# rs485.net
KiCad netlist of a schematic drawn in Altium Designer
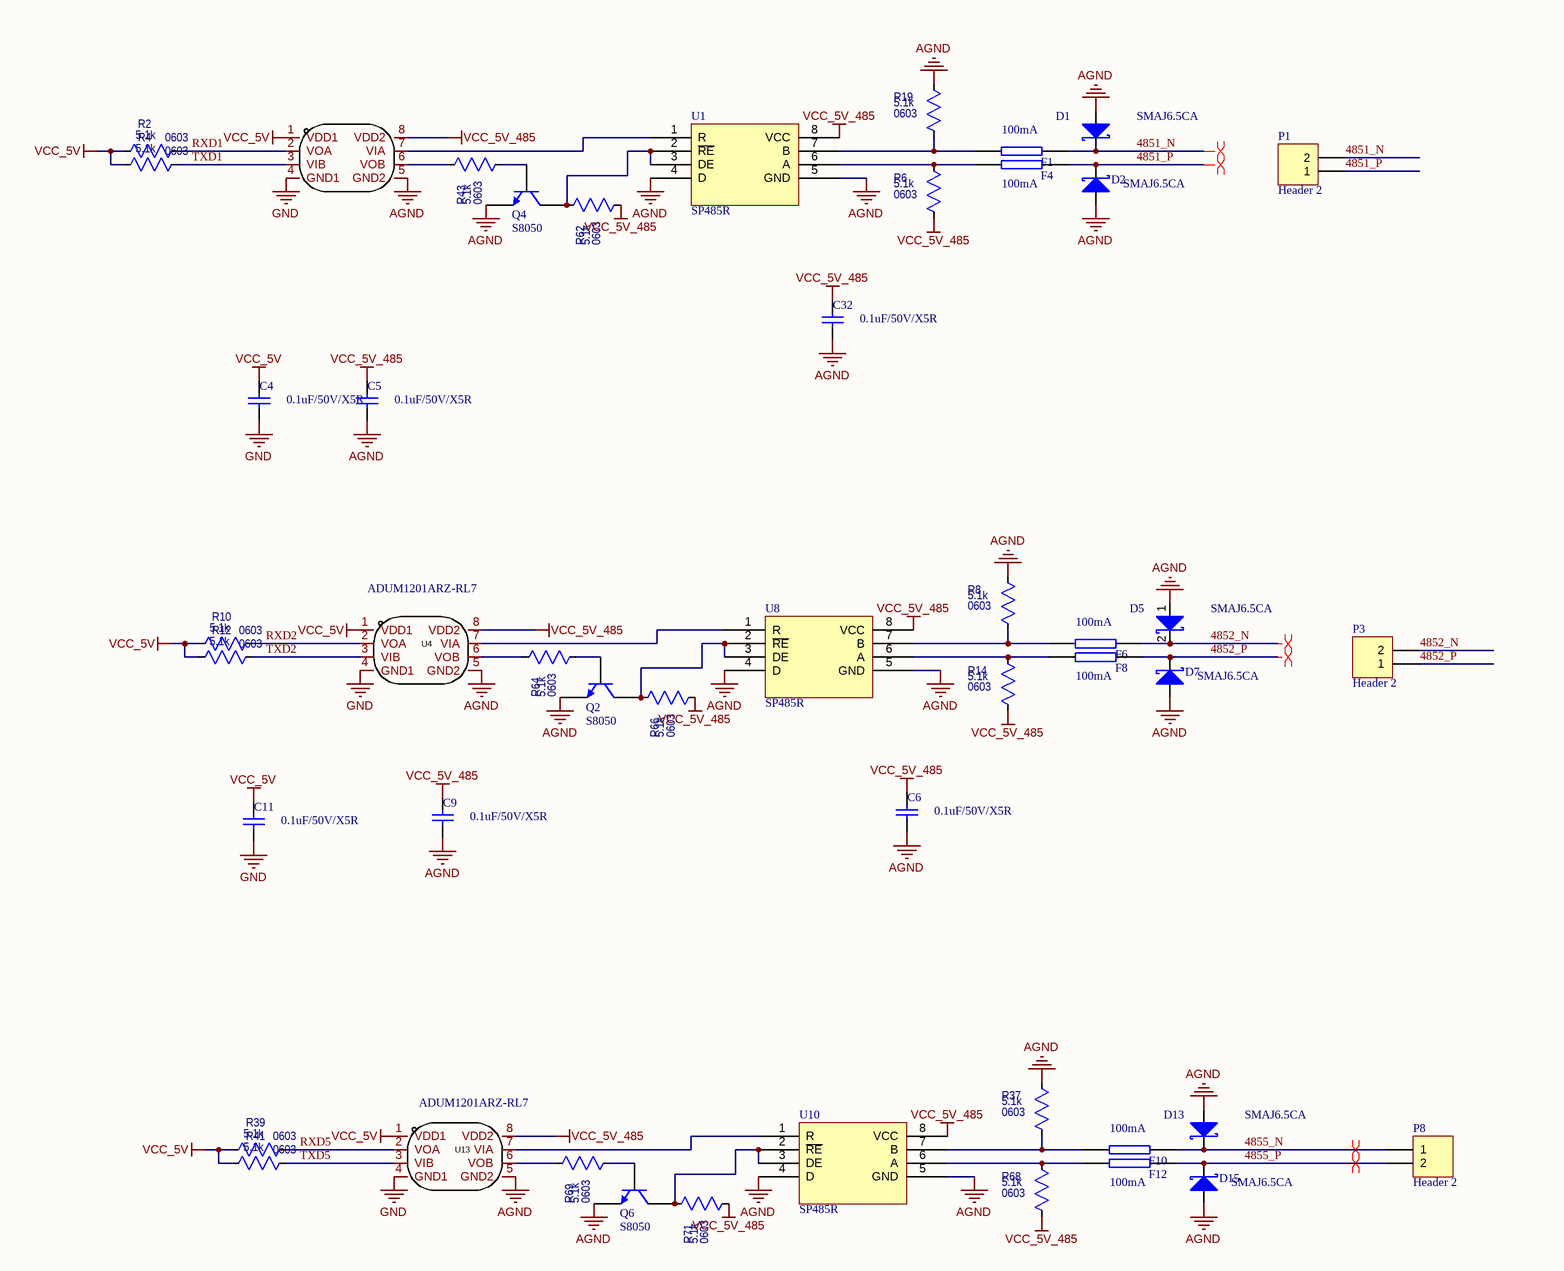
[diagram p0: rs485.SchDoc, top left]
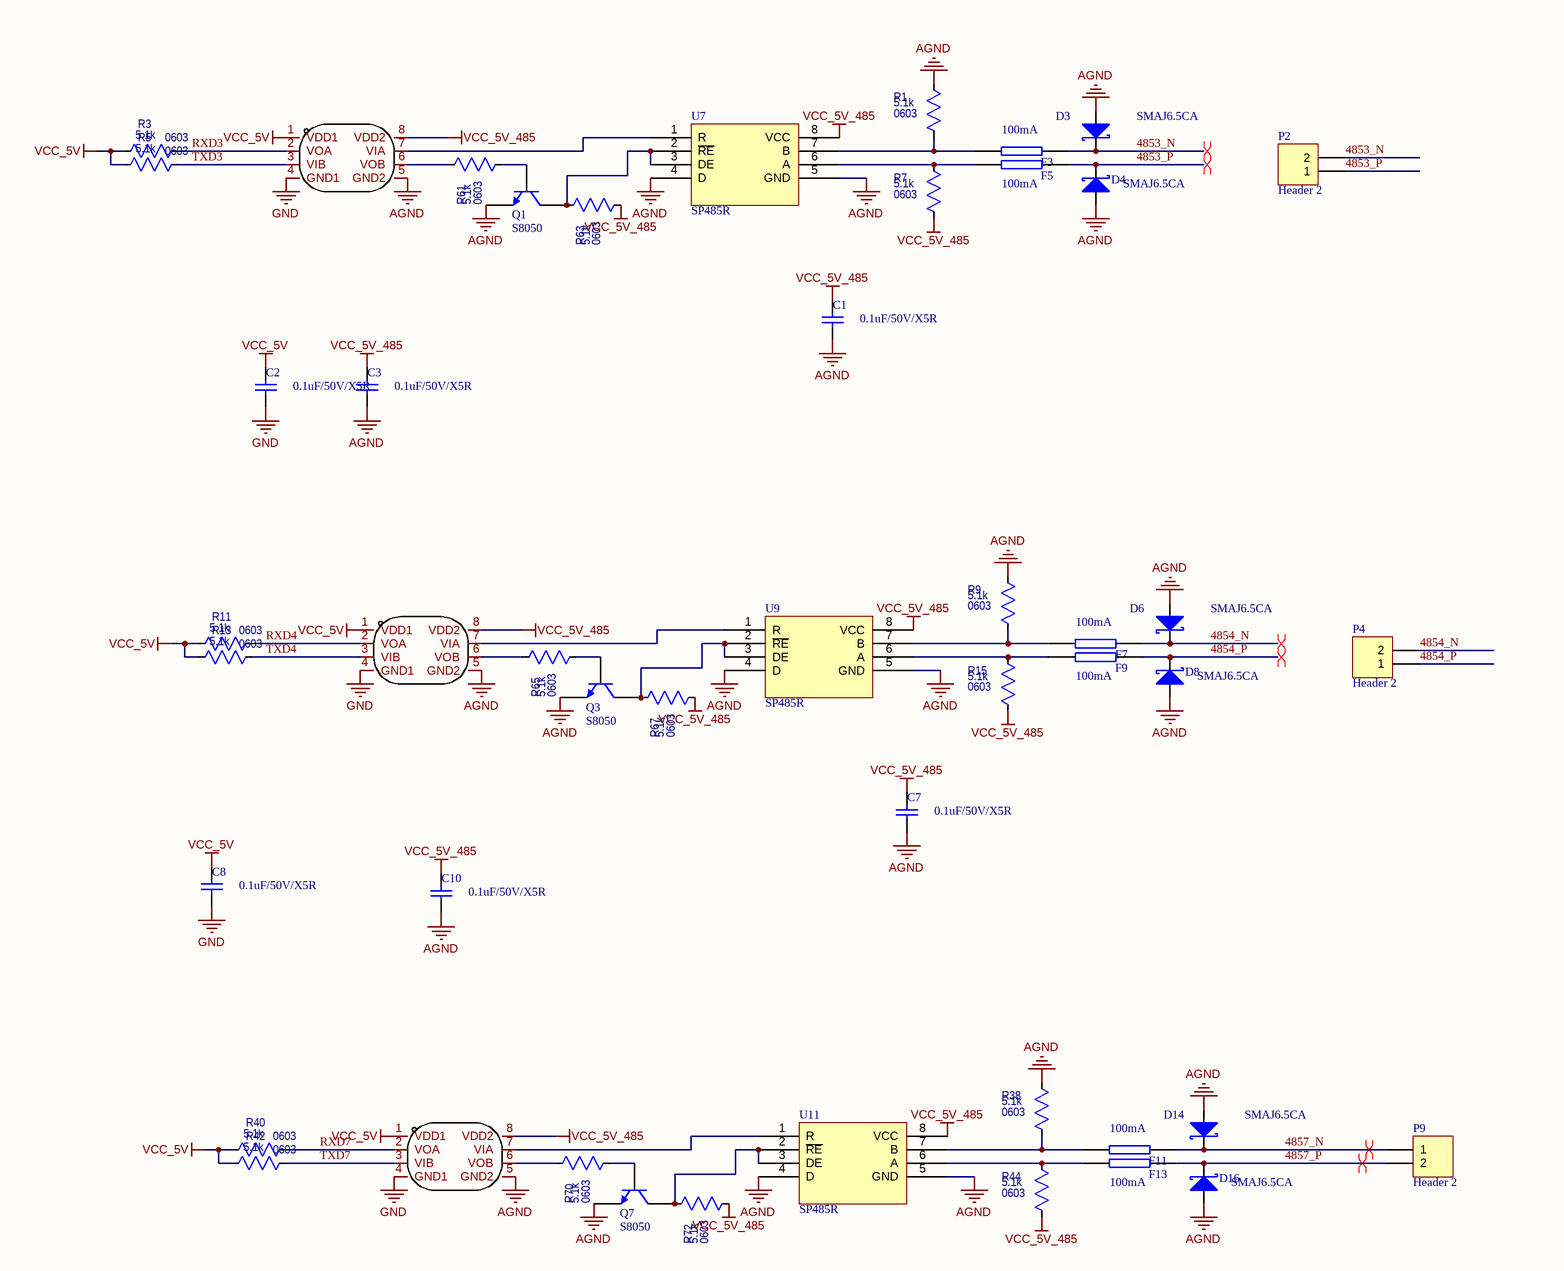
[diagram p1: rs485.SchDoc, top right]
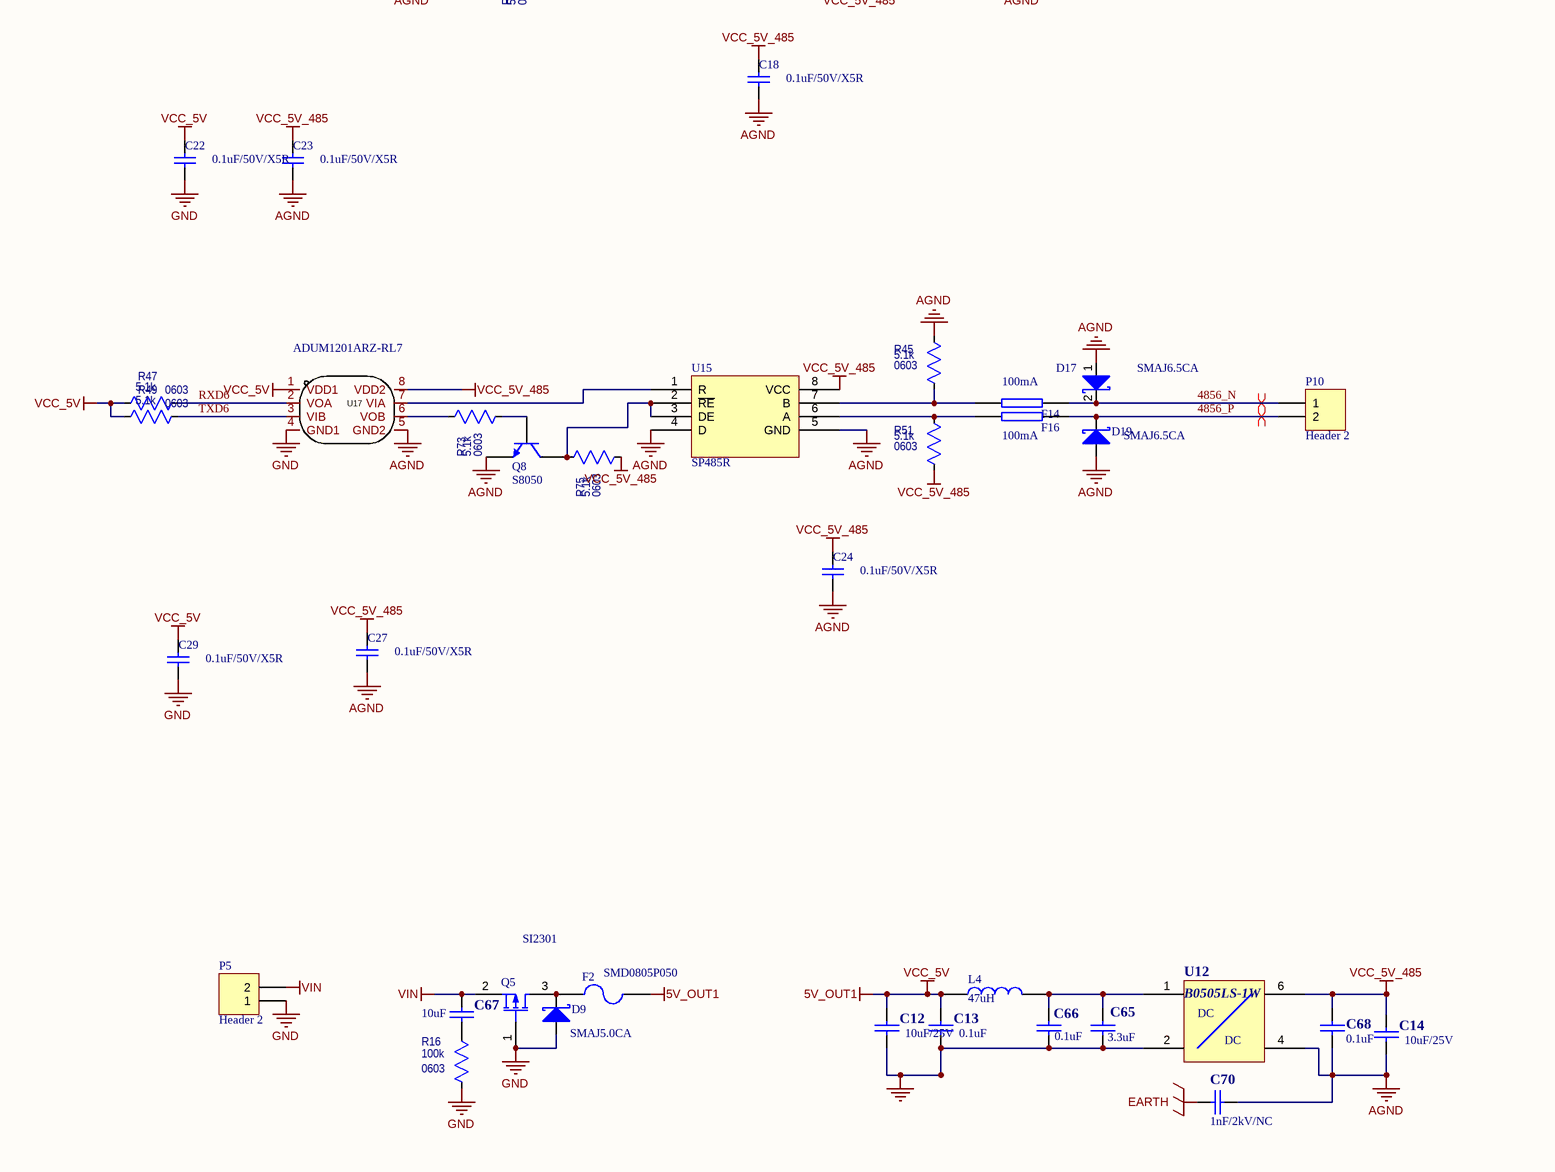
[diagram p2: rs485.SchDoc, bottom left]
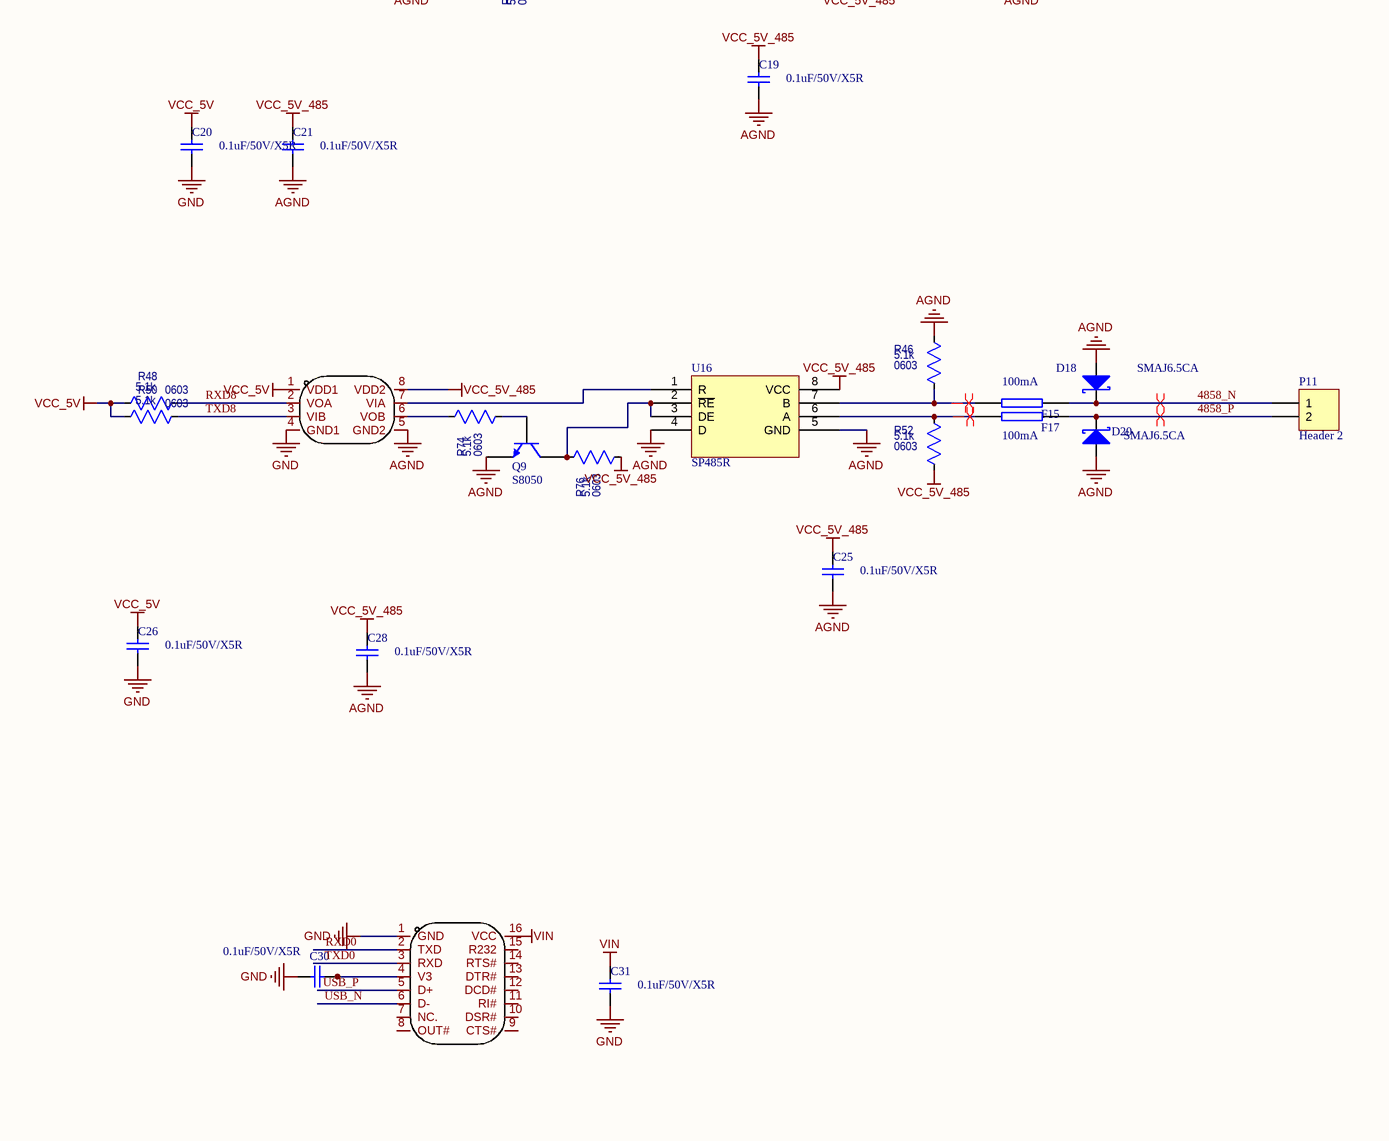
[diagram p3: rs485.SchDoc, bottom right]

(export (version "E")
  (design (tool "Eeschema 10.0.6"))
  (components
    (comp (ref "C1")
      (value "0.1uF/50V/X5R")
      (footprint "0603C")
      (description "贴片电容 20%")
      (libsource (lib "XiaoyI") (part "CAP4"))
    )
    (comp (ref "C2")
      (value "0.1uF/50V/X5R")
      (footprint "0603C")
      (description "贴片电容 20%")
      (libsource (lib "XiaoyI") (part "CAP4"))
    )
    (comp (ref "C3")
      (value "0.1uF/50V/X5R")
      (footprint "0603C")
      (description "贴片电容 20%")
      (libsource (lib "XiaoyI") (part "CAP4"))
    )
    (comp (ref "C4")
      (value "0.1uF/50V/X5R")
      (footprint "0603C")
      (description "贴片电容 20%")
      (libsource (lib "XiaoyI") (part "CAP4"))
    )
    (comp (ref "C5")
      (value "0.1uF/50V/X5R")
      (footprint "0603C")
      (description "贴片电容 20%")
      (libsource (lib "XiaoyI") (part "CAP4"))
    )
    (comp (ref "C6")
      (value "0.1uF/50V/X5R")
      (footprint "0603C")
      (description "贴片电容 20%")
      (libsource (lib "XiaoyI") (part "CAP4"))
    )
    (comp (ref "C7")
      (value "0.1uF/50V/X5R")
      (footprint "0603C")
      (description "贴片电容 20%")
      (libsource (lib "XiaoyI") (part "CAP4"))
    )
    (comp (ref "C8")
      (value "0.1uF/50V/X5R")
      (footprint "0603C")
      (description "贴片电容 20%")
      (libsource (lib "XiaoyI") (part "CAP4"))
    )
    (comp (ref "C9")
      (value "0.1uF/50V/X5R")
      (footprint "0603C")
      (description "贴片电容 20%")
      (libsource (lib "XiaoyI") (part "CAP4"))
    )
    (comp (ref "C10")
      (value "0.1uF/50V/X5R")
      (footprint "0603C")
      (description "贴片电容 20%")
      (libsource (lib "XiaoyI") (part "CAP4"))
    )
    (comp (ref "C11")
      (value "0.1uF/50V/X5R")
      (footprint "0603C")
      (description "贴片电容 20%")
      (libsource (lib "XiaoyI") (part "CAP4"))
    )
    (comp (ref "C12")
      (value "10uF/25V")
      (footprint "0805C")
      (description "Capacitor")
      (libsource (lib "*") (part "CAP"))
    )
    (comp (ref "C13")
      (value "0.1uF")
      (footprint "0603C")
      (description "Capacitor")
      (libsource (lib "*") (part "CAP"))
    )
    (comp (ref "C14")
      (value "10uF/25V")
      (footprint "0805C")
      (description "Capacitor")
      (libsource (lib "*") (part "CAP"))
    )
    (comp (ref "C18")
      (value "0.1uF/50V/X5R")
      (footprint "0603C")
      (description "贴片电容 20%")
      (libsource (lib "XiaoyI") (part "CAP4"))
    )
    (comp (ref "C19")
      (value "0.1uF/50V/X5R")
      (footprint "0603C")
      (description "贴片电容 20%")
      (libsource (lib "XiaoyI") (part "CAP4"))
    )
    (comp (ref "C20")
      (value "0.1uF/50V/X5R")
      (footprint "0603C")
      (description "贴片电容 20%")
      (libsource (lib "XiaoyI") (part "CAP4"))
    )
    (comp (ref "C21")
      (value "0.1uF/50V/X5R")
      (footprint "0603C")
      (description "贴片电容 20%")
      (libsource (lib "XiaoyI") (part "CAP4"))
    )
    (comp (ref "C22")
      (value "0.1uF/50V/X5R")
      (footprint "0603C")
      (description "贴片电容 20%")
      (libsource (lib "XiaoyI") (part "CAP4"))
    )
    (comp (ref "C23")
      (value "0.1uF/50V/X5R")
      (footprint "0603C")
      (description "贴片电容 20%")
      (libsource (lib "XiaoyI") (part "CAP4"))
    )
    (comp (ref "C24")
      (value "0.1uF/50V/X5R")
      (footprint "0603C")
      (description "贴片电容 20%")
      (libsource (lib "XiaoyI") (part "CAP4"))
    )
    (comp (ref "C25")
      (value "0.1uF/50V/X5R")
      (footprint "0603C")
      (description "贴片电容 20%")
      (libsource (lib "XiaoyI") (part "CAP4"))
    )
    (comp (ref "C26")
      (value "0.1uF/50V/X5R")
      (footprint "0603C")
      (description "贴片电容 20%")
      (libsource (lib "XiaoyI") (part "CAP4"))
    )
    (comp (ref "C27")
      (value "0.1uF/50V/X5R")
      (footprint "0603C")
      (description "贴片电容 20%")
      (libsource (lib "XiaoyI") (part "CAP4"))
    )
    (comp (ref "C28")
      (value "0.1uF/50V/X5R")
      (footprint "0603C")
      (description "贴片电容 20%")
      (libsource (lib "XiaoyI") (part "CAP4"))
    )
    (comp (ref "C29")
      (value "0.1uF/50V/X5R")
      (footprint "0603C")
      (description "贴片电容 20%")
      (libsource (lib "XiaoyI") (part "CAP4"))
    )
    (comp (ref "C30")
      (value "0.1uF/50V/X5R")
      (footprint "0603C")
      (description "贴片电容 20%")
      (libsource (lib "XiaoyI") (part "CAP4"))
    )
    (comp (ref "C31")
      (value "0.1uF/50V/X5R")
      (footprint "0603C")
      (description "贴片电容 20%")
      (libsource (lib "XiaoyI") (part "CAP4"))
    )
    (comp (ref "C32")
      (value "0.1uF/50V/X5R")
      (footprint "0603C")
      (description "贴片电容 20%")
      (libsource (lib "XiaoyI") (part "CAP4"))
    )
    (comp (ref "C65")
      (value "3.3uF")
      (footprint "0805C")
      (description "Capacitor")
      (libsource (lib "*") (part "CAP"))
    )
    (comp (ref "C66")
      (value "0.1uF")
      (footprint "0603C")
      (description "Capacitor")
      (libsource (lib "*") (part "CAP"))
    )
    (comp (ref "C67")
      (value "10uF")
      (footprint "0603C")
      (description "Capacitor")
      (libsource (lib "*") (part "CAP"))
    )
    (comp (ref "C68")
      (value "0.1uF")
      (footprint "0603C")
      (description "Capacitor")
      (libsource (lib "*") (part "CAP"))
    )
    (comp (ref "C70")
      (value "1nF/2kV/NC")
      (footprint "1206C")
      (description "Capacitor")
      (libsource (lib "*") (part "CAP"))
    )
    (comp (ref "D1")
      (value "SMAJ6.5CA")
      (footprint "SMA")
      (description "Schottky Diode")
      (libsource (lib "*") (part "DIODE S"))
    )
    (comp (ref "D2")
      (value "SMAJ6.5CA")
      (footprint "SMA")
      (description "Schottky Diode")
      (libsource (lib "*") (part "DIODE S"))
    )
    (comp (ref "D3")
      (value "SMAJ6.5CA")
      (footprint "SMA")
      (description "Schottky Diode")
      (libsource (lib "*") (part "DIODE S"))
    )
    (comp (ref "D4")
      (value "SMAJ6.5CA")
      (footprint "SMA")
      (description "Schottky Diode")
      (libsource (lib "*") (part "DIODE S"))
    )
    (comp (ref "D5")
      (value "SMAJ6.5CA")
      (footprint "SMA")
      (description "Schottky Diode")
      (libsource (lib "") (part "DIODE S_1"))
    )
    (comp (ref "D6")
      (value "SMAJ6.5CA")
      (footprint "SMA")
      (description "Schottky Diode")
      (libsource (lib "*") (part "DIODE S"))
    )
    (comp (ref "D7")
      (value "SMAJ6.5CA")
      (footprint "SMA")
      (description "Schottky Diode")
      (libsource (lib "*") (part "DIODE S"))
    )
    (comp (ref "D8")
      (value "SMAJ6.5CA")
      (footprint "SMA")
      (description "Schottky Diode")
      (libsource (lib "*") (part "DIODE S"))
    )
    (comp (ref "D9")
      (value "SMAJ5.0CA")
      (footprint "SMA")
      (description "Schottky Diode")
      (libsource (lib "*") (part "DIODE S"))
    )
    (comp (ref "D13")
      (value "SMAJ6.5CA")
      (footprint "SMA")
      (description "Schottky Diode")
      (libsource (lib "*") (part "DIODE S"))
    )
    (comp (ref "D14")
      (value "SMAJ6.5CA")
      (footprint "SMA")
      (description "Schottky Diode")
      (libsource (lib "*") (part "DIODE S"))
    )
    (comp (ref "D15")
      (value "SMAJ6.5CA")
      (footprint "SMA")
      (description "Schottky Diode")
      (libsource (lib "*") (part "DIODE S"))
    )
    (comp (ref "D16")
      (value "SMAJ6.5CA")
      (footprint "SMA")
      (description "Schottky Diode")
      (libsource (lib "*") (part "DIODE S"))
    )
    (comp (ref "D17")
      (value "SMAJ6.5CA")
      (footprint "SMA")
      (description "Schottky Diode")
      (libsource (lib "") (part "DIODE S_1"))
    )
    (comp (ref "D18")
      (value "SMAJ6.5CA")
      (footprint "SMA")
      (description "Schottky Diode")
      (libsource (lib "*") (part "DIODE S"))
    )
    (comp (ref "D19")
      (value "SMAJ6.5CA")
      (footprint "SMA")
      (description "Schottky Diode")
      (libsource (lib "*") (part "DIODE S"))
    )
    (comp (ref "D20")
      (value "SMAJ6.5CA")
      (footprint "SMA")
      (description "Schottky Diode")
      (libsource (lib "*") (part "DIODE S"))
    )
    (comp (ref "F1") (value "100mA") (footprint "0805R") (libsource (lib "*") (part "RES2")))
    (comp (ref "F2")
      (value "SMD0805P050")
      (footprint "0805R")
      (description "Fuse")
      (fields (field (name "PUBLISHER") "Altium Limited"))
      (libsource (lib "Miscellaneous Devices") (part "Fuse 2"))
    )
    (comp (ref "F3") (value "100mA") (footprint "0805R") (libsource (lib "*") (part "RES2")))
    (comp (ref "F4") (value "100mA") (footprint "0805R") (libsource (lib "*") (part "RES2")))
    (comp (ref "F5") (value "100mA") (footprint "0805R") (libsource (lib "*") (part "RES2")))
    (comp (ref "F6") (value "100mA") (footprint "0805R") (libsource (lib "*") (part "RES2")))
    (comp (ref "F7") (value "100mA") (footprint "0805R") (libsource (lib "*") (part "RES2")))
    (comp (ref "F8") (value "100mA") (footprint "0805R") (libsource (lib "*") (part "RES2")))
    (comp (ref "F9") (value "100mA") (footprint "0805R") (libsource (lib "*") (part "RES2")))
    (comp (ref "F10") (value "100mA") (footprint "0805R") (libsource (lib "*") (part "RES2")))
    (comp (ref "F11") (value "100mA") (footprint "0805R") (libsource (lib "*") (part "RES2")))
    (comp (ref "F12") (value "100mA") (footprint "0805R") (libsource (lib "*") (part "RES2")))
    (comp (ref "F13") (value "100mA") (footprint "0805R") (libsource (lib "*") (part "RES2")))
    (comp (ref "F14") (value "100mA") (footprint "0805R") (libsource (lib "*") (part "RES2")))
    (comp (ref "F15") (value "100mA") (footprint "0805R") (libsource (lib "*") (part "RES2")))
    (comp (ref "F16") (value "100mA") (footprint "0805R") (libsource (lib "*") (part "RES2")))
    (comp (ref "F17") (value "100mA") (footprint "0805R") (libsource (lib "*") (part "RES2")))
    (comp (ref "L4")
      (value "47uH")
      (footprint "IND-SMD_L7.0-W6.6_FXL0630")
      (libsource (lib "*") (part "INDUCTOR"))
    )
    (comp (ref "P1")
      (value "Header 2")
      (footprint "HDR1X2")
      (description "Header, 2-Pin")
      (fields (field (name "PUBLISHER") "Altium Limited"))
      (libsource (lib "Miscellaneous Connectors") (part "Header 2"))
    )
    (comp (ref "P2")
      (value "Header 2")
      (footprint "HDR1X2")
      (description "Header, 2-Pin")
      (fields (field (name "PUBLISHER") "Altium Limited"))
      (libsource (lib "Miscellaneous Connectors") (part "Header 2"))
    )
    (comp (ref "P3")
      (value "Header 2")
      (footprint "HDR1X2")
      (description "Header, 2-Pin")
      (fields (field (name "PUBLISHER") "Altium Limited"))
      (libsource (lib "Miscellaneous Connectors") (part "Header 2"))
    )
    (comp (ref "P4")
      (value "Header 2")
      (footprint "HDR1X2")
      (description "Header, 2-Pin")
      (fields (field (name "PUBLISHER") "Altium Limited"))
      (libsource (lib "Miscellaneous Connectors") (part "Header 2"))
    )
    (comp (ref "P5")
      (value "Header 2")
      (footprint "HDR1X2")
      (description "Header, 2-Pin")
      (fields (field (name "PUBLISHER") "Altium Limited"))
      (libsource (lib "Miscellaneous Connectors") (part "Header 2"))
    )
    (comp (ref "P8")
      (value "Header 2")
      (footprint "HDR1X2")
      (description "Header, 2-Pin")
      (fields (field (name "PUBLISHER") "Altium Limited"))
      (libsource (lib "") (part "Header 2_1"))
    )
    (comp (ref "P9")
      (value "Header 2")
      (footprint "HDR1X2")
      (description "Header, 2-Pin")
      (fields (field (name "PUBLISHER") "Altium Limited"))
      (libsource (lib "") (part "Header 2_1"))
    )
    (comp (ref "P10")
      (value "Header 2")
      (footprint "HDR1X2")
      (description "Header, 2-Pin")
      (fields (field (name "PUBLISHER") "Altium Limited"))
      (libsource (lib "") (part "Header 2_1"))
    )
    (comp (ref "P11")
      (value "Header 2")
      (footprint "HDR1X2")
      (description "Header, 2-Pin")
      (fields (field (name "PUBLISHER") "Altium Limited"))
      (libsource (lib "") (part "Header 2_1"))
    )
    (comp (ref "Q1")
      (value "S8050")
      (footprint "SOT23-3")
      (description "NPN Bipolar Transistor")
      (fields (field (name "PUBLISHER") "Altium Limited"))
      (libsource (lib "Miscellaneous Devices") (part "NPN"))
    )
    (comp (ref "Q2")
      (value "S8050")
      (footprint "SOT23-3")
      (description "NPN Bipolar Transistor")
      (fields (field (name "PUBLISHER") "Altium Limited"))
      (libsource (lib "Miscellaneous Devices") (part "NPN"))
    )
    (comp (ref "Q3")
      (value "S8050")
      (footprint "SOT23-3")
      (description "NPN Bipolar Transistor")
      (fields (field (name "PUBLISHER") "Altium Limited"))
      (libsource (lib "Miscellaneous Devices") (part "NPN"))
    )
    (comp (ref "Q4")
      (value "S8050")
      (footprint "SOT23-3")
      (description "NPN Bipolar Transistor")
      (fields (field (name "PUBLISHER") "Altium Limited"))
      (libsource (lib "Miscellaneous Devices") (part "NPN"))
    )
    (comp (ref "Q5")
      (value "SI2301")
      (footprint "sot23-3")
      (description "P-Channel MOSFET")
      (fields (field (name "PUBLISHER") "Altium Limited"))
      (libsource (lib "Miscellaneous Devices") (part "MOSFET-P"))
    )
    (comp (ref "Q6")
      (value "S8050")
      (footprint "SOT23-3")
      (description "NPN Bipolar Transistor")
      (fields (field (name "PUBLISHER") "Altium Limited"))
      (libsource (lib "Miscellaneous Devices") (part "NPN"))
    )
    (comp (ref "Q7")
      (value "S8050")
      (footprint "SOT23-3")
      (description "NPN Bipolar Transistor")
      (fields (field (name "PUBLISHER") "Altium Limited"))
      (libsource (lib "Miscellaneous Devices") (part "NPN"))
    )
    (comp (ref "Q8")
      (value "S8050")
      (footprint "SOT23-3")
      (description "NPN Bipolar Transistor")
      (fields (field (name "PUBLISHER") "Altium Limited"))
      (libsource (lib "Miscellaneous Devices") (part "NPN"))
    )
    (comp (ref "Q9")
      (value "S8050")
      (footprint "SOT23-3")
      (description "NPN Bipolar Transistor")
      (fields (field (name "PUBLISHER") "Altium Limited"))
      (libsource (lib "Miscellaneous Devices") (part "NPN"))
    )
    (comp (ref "R1")
      (value "5.1k")
      (footprint "0603r")
      (fields
        (field (name "PARTNUMBER") "RC0603FR-071KL")
        (field (name "TOLERANCE") "tol")
        (field (name "PACKAGE") "0603")
        (field (name "Comment") "10k")
      )
      (libsource (lib "Karl") (part "Resistor_0603"))
    )
    (comp (ref "R2")
      (value "5.1k")
      (footprint "0603r")
      (fields
        (field (name "PARTNUMBER") "RC0603FR-071KL")
        (field (name "TOLERANCE") "tol")
        (field (name "PACKAGE") "0603")
        (field (name "Comment") "10k")
      )
      (libsource (lib "Karl") (part "Resistor_0603"))
    )
    (comp (ref "R3")
      (value "5.1k")
      (footprint "0603r")
      (fields
        (field (name "PARTNUMBER") "RC0603FR-071KL")
        (field (name "TOLERANCE") "tol")
        (field (name "PACKAGE") "0603")
        (field (name "Comment") "10k")
      )
      (libsource (lib "Karl") (part "Resistor_0603"))
    )
    (comp (ref "R4")
      (value "5.1k")
      (footprint "0603r")
      (fields
        (field (name "PARTNUMBER") "RC0603FR-071KL")
        (field (name "TOLERANCE") "tol")
        (field (name "PACKAGE") "0603")
        (field (name "Comment") "10k")
      )
      (libsource (lib "Karl") (part "Resistor_0603"))
    )
    (comp (ref "R5")
      (value "5.1k")
      (footprint "0603r")
      (fields
        (field (name "PARTNUMBER") "RC0603FR-071KL")
        (field (name "TOLERANCE") "tol")
        (field (name "PACKAGE") "0603")
        (field (name "Comment") "10k")
      )
      (libsource (lib "Karl") (part "Resistor_0603"))
    )
    (comp (ref "R6")
      (value "5.1k")
      (footprint "0603r")
      (fields
        (field (name "PARTNUMBER") "RC0603FR-071KL")
        (field (name "TOLERANCE") "tol")
        (field (name "PACKAGE") "0603")
        (field (name "Comment") "10k")
      )
      (libsource (lib "Karl") (part "Resistor_0603"))
    )
    (comp (ref "R7")
      (value "5.1k")
      (footprint "0603r")
      (fields
        (field (name "PARTNUMBER") "RC0603FR-071KL")
        (field (name "TOLERANCE") "tol")
        (field (name "PACKAGE") "0603")
        (field (name "Comment") "10k")
      )
      (libsource (lib "Karl") (part "Resistor_0603"))
    )
    (comp (ref "R8")
      (value "5.1k")
      (footprint "0603r")
      (fields
        (field (name "PARTNUMBER") "RC0603FR-071KL")
        (field (name "TOLERANCE") "tol")
        (field (name "PACKAGE") "0603")
        (field (name "Comment") "10k")
      )
      (libsource (lib "Karl") (part "Resistor_0603"))
    )
    (comp (ref "R9")
      (value "5.1k")
      (footprint "0603r")
      (fields
        (field (name "PARTNUMBER") "RC0603FR-071KL")
        (field (name "TOLERANCE") "tol")
        (field (name "PACKAGE") "0603")
        (field (name "Comment") "10k")
      )
      (libsource (lib "Karl") (part "Resistor_0603"))
    )
    (comp (ref "R10")
      (value "5.1k")
      (footprint "0603r")
      (fields
        (field (name "PARTNUMBER") "RC0603FR-071KL")
        (field (name "TOLERANCE") "tol")
        (field (name "PACKAGE") "0603")
        (field (name "Comment") "10k")
      )
      (libsource (lib "Karl") (part "Resistor_0603"))
    )
    (comp (ref "R11")
      (value "5.1k")
      (footprint "0603r")
      (fields
        (field (name "PARTNUMBER") "RC0603FR-071KL")
        (field (name "TOLERANCE") "tol")
        (field (name "PACKAGE") "0603")
        (field (name "Comment") "10k")
      )
      (libsource (lib "Karl") (part "Resistor_0603"))
    )
    (comp (ref "R12")
      (value "5.1k")
      (footprint "0603r")
      (fields
        (field (name "PARTNUMBER") "RC0603FR-071KL")
        (field (name "TOLERANCE") "tol")
        (field (name "PACKAGE") "0603")
        (field (name "Comment") "10k")
      )
      (libsource (lib "Karl") (part "Resistor_0603"))
    )
    (comp (ref "R13")
      (value "5.1k")
      (footprint "0603r")
      (fields
        (field (name "PARTNUMBER") "RC0603FR-071KL")
        (field (name "TOLERANCE") "tol")
        (field (name "PACKAGE") "0603")
        (field (name "Comment") "10k")
      )
      (libsource (lib "Karl") (part "Resistor_0603"))
    )
    (comp (ref "R14")
      (value "5.1k")
      (footprint "0603r")
      (fields
        (field (name "PARTNUMBER") "RC0603FR-071KL")
        (field (name "TOLERANCE") "tol")
        (field (name "PACKAGE") "0603")
        (field (name "Comment") "10k")
      )
      (libsource (lib "Karl") (part "Resistor_0603"))
    )
    (comp (ref "R15")
      (value "5.1k")
      (footprint "0603r")
      (fields
        (field (name "PARTNUMBER") "RC0603FR-071KL")
        (field (name "TOLERANCE") "tol")
        (field (name "PACKAGE") "0603")
        (field (name "Comment") "10k")
      )
      (libsource (lib "Karl") (part "Resistor_0603"))
    )
    (comp (ref "R16")
      (value "100k")
      (footprint "0603r")
      (fields
        (field (name "PARTNUMBER") "RC0603FR-071KL")
        (field (name "TOLERANCE") "tol")
        (field (name "PACKAGE") "0603")
        (field (name "Comment") "10k")
      )
      (libsource (lib "Karl") (part "Resistor_0603"))
    )
    (comp (ref "R19")
      (value "5.1k")
      (footprint "0603r")
      (fields
        (field (name "PARTNUMBER") "RC0603FR-071KL")
        (field (name "TOLERANCE") "tol")
        (field (name "PACKAGE") "0603")
        (field (name "Comment") "10k")
      )
      (libsource (lib "Karl") (part "Resistor_0603"))
    )
    (comp (ref "R37")
      (value "5.1k")
      (footprint "0603r")
      (fields
        (field (name "PARTNUMBER") "RC0603FR-071KL")
        (field (name "TOLERANCE") "tol")
        (field (name "PACKAGE") "0603")
        (field (name "Comment") "10k")
      )
      (libsource (lib "Karl") (part "Resistor_0603"))
    )
    (comp (ref "R38")
      (value "5.1k")
      (footprint "0603r")
      (fields
        (field (name "PARTNUMBER") "RC0603FR-071KL")
        (field (name "TOLERANCE") "tol")
        (field (name "PACKAGE") "0603")
        (field (name "Comment") "10k")
      )
      (libsource (lib "Karl") (part "Resistor_0603"))
    )
    (comp (ref "R39")
      (value "5.1k")
      (footprint "0603r")
      (fields
        (field (name "PARTNUMBER") "RC0603FR-071KL")
        (field (name "TOLERANCE") "tol")
        (field (name "PACKAGE") "0603")
        (field (name "Comment") "10k")
      )
      (libsource (lib "Karl") (part "Resistor_0603"))
    )
    (comp (ref "R40")
      (value "5.1k")
      (footprint "0603r")
      (fields
        (field (name "PARTNUMBER") "RC0603FR-071KL")
        (field (name "TOLERANCE") "tol")
        (field (name "PACKAGE") "0603")
        (field (name "Comment") "10k")
      )
      (libsource (lib "Karl") (part "Resistor_0603"))
    )
    (comp (ref "R41")
      (value "5.1k")
      (footprint "0603r")
      (fields
        (field (name "PARTNUMBER") "RC0603FR-071KL")
        (field (name "TOLERANCE") "tol")
        (field (name "PACKAGE") "0603")
        (field (name "Comment") "10k")
      )
      (libsource (lib "Karl") (part "Resistor_0603"))
    )
    (comp (ref "R42")
      (value "5.1k")
      (footprint "0603r")
      (fields
        (field (name "PARTNUMBER") "RC0603FR-071KL")
        (field (name "TOLERANCE") "tol")
        (field (name "PACKAGE") "0603")
        (field (name "Comment") "10k")
      )
      (libsource (lib "Karl") (part "Resistor_0603"))
    )
    (comp (ref "R43")
      (value "5.1k")
      (footprint "0603r")
      (fields
        (field (name "PARTNUMBER") "RC0603FR-071KL")
        (field (name "TOLERANCE") "tol")
        (field (name "PACKAGE") "0603")
        (field (name "Comment") "10k")
      )
      (libsource (lib "Karl") (part "Resistor_0603"))
    )
    (comp (ref "R44")
      (value "5.1k")
      (footprint "0603r")
      (fields
        (field (name "PARTNUMBER") "RC0603FR-071KL")
        (field (name "TOLERANCE") "tol")
        (field (name "PACKAGE") "0603")
        (field (name "Comment") "10k")
      )
      (libsource (lib "Karl") (part "Resistor_0603"))
    )
    (comp (ref "R45")
      (value "5.1k")
      (footprint "0603r")
      (fields
        (field (name "PARTNUMBER") "RC0603FR-071KL")
        (field (name "TOLERANCE") "tol")
        (field (name "PACKAGE") "0603")
        (field (name "Comment") "10k")
      )
      (libsource (lib "Karl") (part "Resistor_0603"))
    )
    (comp (ref "R46")
      (value "5.1k")
      (footprint "0603r")
      (fields
        (field (name "PARTNUMBER") "RC0603FR-071KL")
        (field (name "TOLERANCE") "tol")
        (field (name "PACKAGE") "0603")
        (field (name "Comment") "10k")
      )
      (libsource (lib "Karl") (part "Resistor_0603"))
    )
    (comp (ref "R47")
      (value "5.1k")
      (footprint "0603r")
      (fields
        (field (name "PARTNUMBER") "RC0603FR-071KL")
        (field (name "TOLERANCE") "tol")
        (field (name "PACKAGE") "0603")
        (field (name "Comment") "10k")
      )
      (libsource (lib "Karl") (part "Resistor_0603"))
    )
    (comp (ref "R48")
      (value "5.1k")
      (footprint "0603r")
      (fields
        (field (name "PARTNUMBER") "RC0603FR-071KL")
        (field (name "TOLERANCE") "tol")
        (field (name "PACKAGE") "0603")
        (field (name "Comment") "10k")
      )
      (libsource (lib "Karl") (part "Resistor_0603"))
    )
    (comp (ref "R49")
      (value "5.1k")
      (footprint "0603r")
      (fields
        (field (name "PARTNUMBER") "RC0603FR-071KL")
        (field (name "TOLERANCE") "tol")
        (field (name "PACKAGE") "0603")
        (field (name "Comment") "10k")
      )
      (libsource (lib "Karl") (part "Resistor_0603"))
    )
    (comp (ref "R50")
      (value "5.1k")
      (footprint "0603r")
      (fields
        (field (name "PARTNUMBER") "RC0603FR-071KL")
        (field (name "TOLERANCE") "tol")
        (field (name "PACKAGE") "0603")
        (field (name "Comment") "10k")
      )
      (libsource (lib "Karl") (part "Resistor_0603"))
    )
    (comp (ref "R51")
      (value "5.1k")
      (footprint "0603r")
      (fields
        (field (name "PARTNUMBER") "RC0603FR-071KL")
        (field (name "TOLERANCE") "tol")
        (field (name "PACKAGE") "0603")
        (field (name "Comment") "10k")
      )
      (libsource (lib "Karl") (part "Resistor_0603"))
    )
    (comp (ref "R52")
      (value "5.1k")
      (footprint "0603r")
      (fields
        (field (name "PARTNUMBER") "RC0603FR-071KL")
        (field (name "TOLERANCE") "tol")
        (field (name "PACKAGE") "0603")
        (field (name "Comment") "10k")
      )
      (libsource (lib "Karl") (part "Resistor_0603"))
    )
    (comp (ref "R61")
      (value "5.1k")
      (footprint "0603r")
      (fields
        (field (name "PARTNUMBER") "RC0603FR-071KL")
        (field (name "TOLERANCE") "tol")
        (field (name "PACKAGE") "0603")
        (field (name "Comment") "10k")
      )
      (libsource (lib "Karl") (part "Resistor_0603"))
    )
    (comp (ref "R62")
      (value "5.1k")
      (footprint "0603r")
      (fields
        (field (name "PARTNUMBER") "RC0603FR-071KL")
        (field (name "TOLERANCE") "tol")
        (field (name "PACKAGE") "0603")
        (field (name "Comment") "10k")
      )
      (libsource (lib "Karl") (part "Resistor_0603"))
    )
    (comp (ref "R63")
      (value "5.1k")
      (footprint "0603r")
      (fields
        (field (name "PARTNUMBER") "RC0603FR-071KL")
        (field (name "TOLERANCE") "tol")
        (field (name "PACKAGE") "0603")
        (field (name "Comment") "10k")
      )
      (libsource (lib "Karl") (part "Resistor_0603"))
    )
    (comp (ref "R64")
      (value "5.1k")
      (footprint "0603r")
      (fields
        (field (name "PARTNUMBER") "RC0603FR-071KL")
        (field (name "TOLERANCE") "tol")
        (field (name "PACKAGE") "0603")
        (field (name "Comment") "10k")
      )
      (libsource (lib "Karl") (part "Resistor_0603"))
    )
    (comp (ref "R65")
      (value "5.1k")
      (footprint "0603r")
      (fields
        (field (name "PARTNUMBER") "RC0603FR-071KL")
        (field (name "TOLERANCE") "tol")
        (field (name "PACKAGE") "0603")
        (field (name "Comment") "10k")
      )
      (libsource (lib "Karl") (part "Resistor_0603"))
    )
    (comp (ref "R66")
      (value "5.1k")
      (footprint "0603r")
      (fields
        (field (name "PARTNUMBER") "RC0603FR-071KL")
        (field (name "TOLERANCE") "tol")
        (field (name "PACKAGE") "0603")
        (field (name "Comment") "10k")
      )
      (libsource (lib "Karl") (part "Resistor_0603"))
    )
    (comp (ref "R67")
      (value "5.1k")
      (footprint "0603r")
      (fields
        (field (name "PARTNUMBER") "RC0603FR-071KL")
        (field (name "TOLERANCE") "tol")
        (field (name "PACKAGE") "0603")
        (field (name "Comment") "10k")
      )
      (libsource (lib "Karl") (part "Resistor_0603"))
    )
    (comp (ref "R68")
      (value "5.1k")
      (footprint "0603r")
      (fields
        (field (name "PARTNUMBER") "RC0603FR-071KL")
        (field (name "TOLERANCE") "tol")
        (field (name "PACKAGE") "0603")
        (field (name "Comment") "10k")
      )
      (libsource (lib "Karl") (part "Resistor_0603"))
    )
    (comp (ref "R69")
      (value "5.1k")
      (footprint "0603r")
      (fields
        (field (name "PARTNUMBER") "RC0603FR-071KL")
        (field (name "TOLERANCE") "tol")
        (field (name "PACKAGE") "0603")
        (field (name "Comment") "10k")
      )
      (libsource (lib "Karl") (part "Resistor_0603"))
    )
    (comp (ref "R70")
      (value "5.1k")
      (footprint "0603r")
      (fields
        (field (name "PARTNUMBER") "RC0603FR-071KL")
        (field (name "TOLERANCE") "tol")
        (field (name "PACKAGE") "0603")
        (field (name "Comment") "10k")
      )
      (libsource (lib "Karl") (part "Resistor_0603"))
    )
    (comp (ref "R71")
      (value "5.1k")
      (footprint "0603r")
      (fields
        (field (name "PARTNUMBER") "RC0603FR-071KL")
        (field (name "TOLERANCE") "tol")
        (field (name "PACKAGE") "0603")
        (field (name "Comment") "10k")
      )
      (libsource (lib "Karl") (part "Resistor_0603"))
    )
    (comp (ref "R72")
      (value "5.1k")
      (footprint "0603r")
      (fields
        (field (name "PARTNUMBER") "RC0603FR-071KL")
        (field (name "TOLERANCE") "tol")
        (field (name "PACKAGE") "0603")
        (field (name "Comment") "10k")
      )
      (libsource (lib "Karl") (part "Resistor_0603"))
    )
    (comp (ref "R73")
      (value "5.1k")
      (footprint "0603r")
      (fields
        (field (name "PARTNUMBER") "RC0603FR-071KL")
        (field (name "TOLERANCE") "tol")
        (field (name "PACKAGE") "0603")
        (field (name "Comment") "10k")
      )
      (libsource (lib "Karl") (part "Resistor_0603"))
    )
    (comp (ref "R74")
      (value "5.1k")
      (footprint "0603r")
      (fields
        (field (name "PARTNUMBER") "RC0603FR-071KL")
        (field (name "TOLERANCE") "tol")
        (field (name "PACKAGE") "0603")
        (field (name "Comment") "10k")
      )
      (libsource (lib "Karl") (part "Resistor_0603"))
    )
    (comp (ref "R75")
      (value "5.1k")
      (footprint "0603r")
      (fields
        (field (name "PARTNUMBER") "RC0603FR-071KL")
        (field (name "TOLERANCE") "tol")
        (field (name "PACKAGE") "0603")
        (field (name "Comment") "10k")
      )
      (libsource (lib "Karl") (part "Resistor_0603"))
    )
    (comp (ref "R76")
      (value "5.1k")
      (footprint "0603r")
      (fields
        (field (name "PARTNUMBER") "RC0603FR-071KL")
        (field (name "TOLERANCE") "tol")
        (field (name "PACKAGE") "0603")
        (field (name "Comment") "10k")
      )
      (libsource (lib "Karl") (part "Resistor_0603"))
    )
    (comp (ref "U1") (value "SP485R") (footprint "so-8") (libsource (lib "Schlib1") (part "SN65HVD06D")))
    (comp (ref "U2")
      (value "ADUM1201ARZ-RL7")
      (footprint "SO8")
      (libsource (lib "altium-import") (part "root_0_ADUM1201ARZ-RL7_"))
    )
    (comp (ref "U3")
      (value "ADUM1201ARZ-RL7")
      (footprint "SO-8")
      (libsource (lib "altium-import") (part "root_0_ADUM1201ARZ-RL7_"))
    )
    (comp (ref "U4")
      (value "ADUM1201ARZ-RL7")
      (footprint "SO-8")
      (libsource (lib "altium-import") (part "root_0_ADUM1201ARZ-RL7_"))
    )
    (comp (ref "U5")
      (value "ADUM1201ARZ-RL7")
      (footprint "SO-8")
      (libsource (lib "altium-import") (part "root_0_ADUM1201ARZ-RL7_"))
    )
    (comp (ref "U7") (value "SP485R") (footprint "so-8") (libsource (lib "Schlib1") (part "SN65HVD06D")))
    (comp (ref "U8") (value "SP485R") (footprint "so-8") (libsource (lib "Schlib1") (part "SN65HVD06D")))
    (comp (ref "U9") (value "SP485R") (footprint "so-8") (libsource (lib "Schlib1") (part "SN65HVD06D")))
    (comp (ref "U10") (value "SP485R") (footprint "so-8") (libsource (lib "Schlib1") (part "SN65HVD06D")))
    (comp (ref "U11") (value "SP485R") (footprint "so-8") (libsource (lib "Schlib1") (part "SN65HVD06D")))
    (comp (ref "U12")
      (value "B0505LS-1W")
      (footprint "PWRM-TH_4P-L19.7-W6.0-P2.54")
      (libsource (lib "*") (part "B0505S"))
    )
    (comp (ref "U13")
      (value "ADUM1201ARZ-RL7")
      (footprint "SO-8")
      (libsource (lib "altium-import") (part "root_0_ADUM1201ARZ-RL7_"))
    )
    (comp (ref "U14")
      (value "ADUM1201ARZ-RL7")
      (footprint "SO-8")
      (libsource (lib "altium-import") (part "root_0_ADUM1201ARZ-RL7_"))
    )
    (comp (ref "U15") (value "SP485R") (footprint "so-8") (libsource (lib "Schlib1") (part "SN65HVD06D")))
    (comp (ref "U16") (value "SP485R") (footprint "so-8") (libsource (lib "Schlib1") (part "SN65HVD06D")))
    (comp (ref "U17")
      (value "ADUM1201ARZ-RL7")
      (footprint "SO-8")
      (libsource (lib "altium-import") (part "root_0_ADUM1201ARZ-RL7_"))
    )
    (comp (ref "U18")
      (value "ADUM1201ARZ-RL7")
      (footprint "SO-8")
      (libsource (lib "altium-import") (part "root_0_ADUM1201ARZ-RL7_"))
    )
    (comp (ref "U19")
      (value "CH340C")
      (footprint "SOP-16_L10.0-W3.9-P1.27-LS6.0-BL")
      (libsource (lib "altium-import") (part "root_0_CH340C_"))
    )
  )
  (nets
    (net (code "1") (name "/4851_N") (class "Default")
      (node (ref "D1") (pin "2") (pinfunction "K_2") (pintype "passive"))
      (node (ref "F1") (pin "1") (pinfunction "1_1") (pintype "passive"))
      (node (ref "P1") (pin "2") (pinfunction "2_2") (pintype "passive"))
    )
    (net (code "2") (name "/4851_P") (class "Default")
      (node (ref "D2") (pin "2") (pinfunction "K_2") (pintype "passive"))
      (node (ref "F4") (pin "1") (pinfunction "1_1") (pintype "passive"))
      (node (ref "P1") (pin "1") (pinfunction "1_1") (pintype "passive"))
    )
    (net (code "3") (name "/4852_N") (class "Default")
      (node (ref "D5") (pin "2") (pinfunction "K_2") (pintype "passive"))
      (node (ref "F6") (pin "1") (pinfunction "1_1") (pintype "passive"))
      (node (ref "P3") (pin "2") (pinfunction "2_2") (pintype "passive"))
    )
    (net (code "4") (name "/4852_P") (class "Default")
      (node (ref "D7") (pin "2") (pinfunction "K_2") (pintype "passive"))
      (node (ref "F8") (pin "1") (pinfunction "1_1") (pintype "passive"))
      (node (ref "P3") (pin "1") (pinfunction "1_1") (pintype "passive"))
    )
    (net (code "5") (name "/4853_N") (class "Default")
      (node (ref "D3") (pin "2") (pinfunction "K_2") (pintype "passive"))
      (node (ref "F3") (pin "1") (pinfunction "1_1") (pintype "passive"))
      (node (ref "P2") (pin "2") (pinfunction "2_2") (pintype "passive"))
    )
    (net (code "6") (name "/4853_P") (class "Default")
      (node (ref "D4") (pin "2") (pinfunction "K_2") (pintype "passive"))
      (node (ref "F5") (pin "1") (pinfunction "1_1") (pintype "passive"))
      (node (ref "P2") (pin "1") (pinfunction "1_1") (pintype "passive"))
    )
    (net (code "7") (name "/4854_N") (class "Default")
      (node (ref "D6") (pin "2") (pinfunction "K_2") (pintype "passive"))
      (node (ref "F7") (pin "1") (pinfunction "1_1") (pintype "passive"))
      (node (ref "P4") (pin "2") (pinfunction "2_2") (pintype "passive"))
    )
    (net (code "8") (name "/4854_P") (class "Default")
      (node (ref "D8") (pin "2") (pinfunction "K_2") (pintype "passive"))
      (node (ref "F9") (pin "1") (pinfunction "1_1") (pintype "passive"))
      (node (ref "P4") (pin "1") (pinfunction "1_1") (pintype "passive"))
    )
    (net (code "9") (name "/4855_N") (class "Default")
      (node (ref "D13") (pin "2") (pinfunction "K_2") (pintype "passive"))
      (node (ref "F10") (pin "1") (pinfunction "1_1") (pintype "passive"))
      (node (ref "P8") (pin "1") (pinfunction "1_1") (pintype "passive"))
    )
    (net (code "10") (name "/4855_P") (class "Default")
      (node (ref "D15") (pin "2") (pinfunction "K_2") (pintype "passive"))
      (node (ref "F12") (pin "1") (pinfunction "1_1") (pintype "passive"))
      (node (ref "P8") (pin "2") (pinfunction "2_2") (pintype "passive"))
    )
    (net (code "11") (name "/4856_N") (class "Default")
      (node (ref "D17") (pin "2") (pinfunction "K_2") (pintype "passive"))
      (node (ref "F14") (pin "1") (pinfunction "1_1") (pintype "passive"))
      (node (ref "P10") (pin "1") (pinfunction "1_1") (pintype "passive"))
    )
    (net (code "12") (name "/4856_P") (class "Default")
      (node (ref "D19") (pin "2") (pinfunction "K_2") (pintype "passive"))
      (node (ref "F16") (pin "1") (pinfunction "1_1") (pintype "passive"))
      (node (ref "P10") (pin "2") (pinfunction "2_2") (pintype "passive"))
    )
    (net (code "13") (name "/4857_N") (class "Default")
      (node (ref "D14") (pin "2") (pinfunction "K_2") (pintype "passive"))
      (node (ref "F11") (pin "1") (pinfunction "1_1") (pintype "passive"))
      (node (ref "P9") (pin "1") (pinfunction "1_1") (pintype "passive"))
    )
    (net (code "14") (name "/4857_P") (class "Default")
      (node (ref "D16") (pin "2") (pinfunction "K_2") (pintype "passive"))
      (node (ref "F13") (pin "1") (pinfunction "1_1") (pintype "passive"))
      (node (ref "P9") (pin "2") (pinfunction "2_2") (pintype "passive"))
    )
    (net (code "15") (name "/4858_N") (class "Default")
      (node (ref "D18") (pin "2") (pinfunction "K_2") (pintype "passive"))
      (node (ref "F15") (pin "1") (pinfunction "1_1") (pintype "passive"))
      (node (ref "P11") (pin "1") (pinfunction "1_1") (pintype "passive"))
    )
    (net (code "16") (name "/4858_P") (class "Default")
      (node (ref "D20") (pin "2") (pinfunction "K_2") (pintype "passive"))
      (node (ref "F17") (pin "1") (pinfunction "1_1") (pintype "passive"))
      (node (ref "P11") (pin "2") (pinfunction "2_2") (pintype "passive"))
    )
    (net (code "17") (name "/RXD0") (class "Default")
      (node (ref "U19") (pin "2") (pinfunction "TXD_2") (pintype "passive"))
    )
    (net (code "18") (name "/RXD1") (class "Default")
      (node (ref "R2") (pin "2") (pinfunction "2_2") (pintype "passive"))
      (node (ref "U2") (pin "2") (pinfunction "VOA_2") (pintype "passive"))
    )
    (net (code "19") (name "/RXD2") (class "Default")
      (node (ref "R10") (pin "2") (pinfunction "2_2") (pintype "passive"))
      (node (ref "U4") (pin "2") (pinfunction "VOA_2") (pintype "passive"))
    )
    (net (code "20") (name "/RXD3") (class "Default")
      (node (ref "R3") (pin "2") (pinfunction "2_2") (pintype "passive"))
      (node (ref "U3") (pin "2") (pinfunction "VOA_2") (pintype "passive"))
    )
    (net (code "21") (name "/RXD4") (class "Default")
      (node (ref "R11") (pin "2") (pinfunction "2_2") (pintype "passive"))
      (node (ref "U5") (pin "2") (pinfunction "VOA_2") (pintype "passive"))
    )
    (net (code "22") (name "/RXD5") (class "Default")
      (node (ref "R39") (pin "2") (pinfunction "2_2") (pintype "passive"))
      (node (ref "U13") (pin "2") (pinfunction "VOA_2") (pintype "passive"))
    )
    (net (code "23") (name "/RXD6") (class "Default")
      (node (ref "R47") (pin "2") (pinfunction "2_2") (pintype "passive"))
      (node (ref "U17") (pin "2") (pinfunction "VOA_2") (pintype "passive"))
    )
    (net (code "24") (name "/RXD7") (class "Default")
      (node (ref "R40") (pin "2") (pinfunction "2_2") (pintype "passive"))
      (node (ref "U14") (pin "2") (pinfunction "VOA_2") (pintype "passive"))
    )
    (net (code "25") (name "/RXD8") (class "Default")
      (node (ref "R48") (pin "2") (pinfunction "2_2") (pintype "passive"))
      (node (ref "U18") (pin "2") (pinfunction "VOA_2") (pintype "passive"))
    )
    (net (code "26") (name "/TXD0") (class "Default")
      (node (ref "U19") (pin "3") (pinfunction "RXD_3") (pintype "passive"))
    )
    (net (code "27") (name "/TXD1") (class "Default")
      (node (ref "R4") (pin "2") (pinfunction "2_2") (pintype "passive"))
      (node (ref "U2") (pin "3") (pinfunction "VIB_3") (pintype "passive"))
    )
    (net (code "28") (name "/TXD2") (class "Default")
      (node (ref "R12") (pin "2") (pinfunction "2_2") (pintype "passive"))
      (node (ref "U4") (pin "3") (pinfunction "VIB_3") (pintype "passive"))
    )
    (net (code "29") (name "/TXD3") (class "Default")
      (node (ref "R5") (pin "2") (pinfunction "2_2") (pintype "passive"))
      (node (ref "U3") (pin "3") (pinfunction "VIB_3") (pintype "passive"))
    )
    (net (code "30") (name "/TXD4") (class "Default")
      (node (ref "R13") (pin "2") (pinfunction "2_2") (pintype "passive"))
      (node (ref "U5") (pin "3") (pinfunction "VIB_3") (pintype "passive"))
    )
    (net (code "31") (name "/TXD5") (class "Default")
      (node (ref "R41") (pin "2") (pinfunction "2_2") (pintype "passive"))
      (node (ref "U13") (pin "3") (pinfunction "VIB_3") (pintype "passive"))
    )
    (net (code "32") (name "/TXD6") (class "Default")
      (node (ref "R49") (pin "2") (pinfunction "2_2") (pintype "passive"))
      (node (ref "U17") (pin "3") (pinfunction "VIB_3") (pintype "passive"))
    )
    (net (code "33") (name "/TXD7") (class "Default")
      (node (ref "R42") (pin "2") (pinfunction "2_2") (pintype "passive"))
      (node (ref "U14") (pin "3") (pinfunction "VIB_3") (pintype "passive"))
    )
    (net (code "34") (name "/TXD8") (class "Default")
      (node (ref "R50") (pin "2") (pinfunction "2_2") (pintype "passive"))
      (node (ref "U18") (pin "3") (pinfunction "VIB_3") (pintype "passive"))
    )
    (net (code "35") (name "/USB_N") (class "Default")
      (node (ref "U19") (pin "6") (pinfunction "D-_6") (pintype "passive"))
    )
    (net (code "36") (name "/USB_P") (class "Default")
      (node (ref "U19") (pin "5") (pinfunction "D+_5") (pintype "passive"))
    )
    (net (code "37") (name "5V_OUT1") (class "Default")
      (node (ref "C11") (pin "2") (pinfunction "2_2") (pintype "passive"))
      (node (ref "C12") (pin "1") (pinfunction "1_1") (pintype "passive"))
      (node (ref "C13") (pin "1") (pinfunction "1_1") (pintype "passive"))
      (node (ref "C2") (pin "2") (pinfunction "2_2") (pintype "passive"))
      (node (ref "C20") (pin "2") (pinfunction "2_2") (pintype "passive"))
      (node (ref "C22") (pin "2") (pinfunction "2_2") (pintype "passive"))
      (node (ref "C26") (pin "2") (pinfunction "2_2") (pintype "passive"))
      (node (ref "C29") (pin "2") (pinfunction "2_2") (pintype "passive"))
      (node (ref "C4") (pin "2") (pinfunction "2_2") (pintype "passive"))
      (node (ref "C8") (pin "2") (pinfunction "2_2") (pintype "passive"))
      (node (ref "F2") (pin "2") (pinfunction "2_2") (pintype "passive"))
      (node (ref "L4") (pin "1") (pinfunction "1_1") (pintype "passive"))
      (node (ref "R10") (pin "1") (pinfunction "1_1") (pintype "passive"))
      (node (ref "R11") (pin "1") (pinfunction "1_1") (pintype "passive"))
      (node (ref "R12") (pin "1") (pinfunction "1_1") (pintype "passive"))
      (node (ref "R13") (pin "1") (pinfunction "1_1") (pintype "passive"))
      (node (ref "R2") (pin "1") (pinfunction "1_1") (pintype "passive"))
      (node (ref "R3") (pin "1") (pinfunction "1_1") (pintype "passive"))
      (node (ref "R39") (pin "1") (pinfunction "1_1") (pintype "passive"))
      (node (ref "R4") (pin "1") (pinfunction "1_1") (pintype "passive"))
      (node (ref "R40") (pin "1") (pinfunction "1_1") (pintype "passive"))
      (node (ref "R41") (pin "1") (pinfunction "1_1") (pintype "passive"))
      (node (ref "R42") (pin "1") (pinfunction "1_1") (pintype "passive"))
      (node (ref "R47") (pin "1") (pinfunction "1_1") (pintype "passive"))
      (node (ref "R48") (pin "1") (pinfunction "1_1") (pintype "passive"))
      (node (ref "R49") (pin "1") (pinfunction "1_1") (pintype "passive"))
      (node (ref "R5") (pin "1") (pinfunction "1_1") (pintype "passive"))
      (node (ref "R50") (pin "1") (pinfunction "1_1") (pintype "passive"))
      (node (ref "U13") (pin "1") (pinfunction "VDD1_1") (pintype "passive"))
      (node (ref "U14") (pin "1") (pinfunction "VDD1_1") (pintype "passive"))
      (node (ref "U17") (pin "1") (pinfunction "VDD1_1") (pintype "passive"))
      (node (ref "U18") (pin "1") (pinfunction "VDD1_1") (pintype "passive"))
      (node (ref "U2") (pin "1") (pinfunction "VDD1_1") (pintype "passive"))
      (node (ref "U3") (pin "1") (pinfunction "VDD1_1") (pintype "passive"))
      (node (ref "U4") (pin "1") (pinfunction "VDD1_1") (pintype "passive"))
      (node (ref "U5") (pin "1") (pinfunction "VDD1_1") (pintype "passive"))
    )
    (net (code "38") (name "AGND") (class "Default")
      (node (ref "C1") (pin "1") (pinfunction "1_1") (pintype "passive"))
      (node (ref "C10") (pin "1") (pinfunction "1_1") (pintype "passive"))
      (node (ref "C14") (pin "2") (pinfunction "2_2") (pintype "passive"))
      (node (ref "C18") (pin "1") (pinfunction "1_1") (pintype "passive"))
      (node (ref "C19") (pin "1") (pinfunction "1_1") (pintype "passive"))
      (node (ref "C21") (pin "1") (pinfunction "1_1") (pintype "passive"))
      (node (ref "C23") (pin "1") (pinfunction "1_1") (pintype "passive"))
      (node (ref "C24") (pin "1") (pinfunction "1_1") (pintype "passive"))
      (node (ref "C25") (pin "1") (pinfunction "1_1") (pintype "passive"))
      (node (ref "C27") (pin "1") (pinfunction "1_1") (pintype "passive"))
      (node (ref "C28") (pin "1") (pinfunction "1_1") (pintype "passive"))
      (node (ref "C3") (pin "1") (pinfunction "1_1") (pintype "passive"))
      (node (ref "C32") (pin "1") (pinfunction "1_1") (pintype "passive"))
      (node (ref "C5") (pin "1") (pinfunction "1_1") (pintype "passive"))
      (node (ref "C6") (pin "1") (pinfunction "1_1") (pintype "passive"))
      (node (ref "C68") (pin "2") (pinfunction "2_2") (pintype "passive"))
      (node (ref "C7") (pin "1") (pinfunction "1_1") (pintype "passive"))
      (node (ref "C70") (pin "1") (pinfunction "1_1") (pintype "passive"))
      (node (ref "C9") (pin "1") (pinfunction "1_1") (pintype "passive"))
      (node (ref "D1") (pin "1") (pinfunction "A_1") (pintype "passive"))
      (node (ref "D13") (pin "1") (pinfunction "A_1") (pintype "passive"))
      (node (ref "D14") (pin "1") (pinfunction "A_1") (pintype "passive"))
      (node (ref "D15") (pin "1") (pinfunction "A_1") (pintype "passive"))
      (node (ref "D16") (pin "1") (pinfunction "A_1") (pintype "passive"))
      (node (ref "D17") (pin "1") (pinfunction "A_1") (pintype "passive"))
      (node (ref "D18") (pin "1") (pinfunction "A_1") (pintype "passive"))
      (node (ref "D19") (pin "1") (pinfunction "A_1") (pintype "passive"))
      (node (ref "D2") (pin "1") (pinfunction "A_1") (pintype "passive"))
      (node (ref "D20") (pin "1") (pinfunction "A_1") (pintype "passive"))
      (node (ref "D3") (pin "1") (pinfunction "A_1") (pintype "passive"))
      (node (ref "D4") (pin "1") (pinfunction "A_1") (pintype "passive"))
      (node (ref "D5") (pin "1") (pinfunction "A_1") (pintype "passive"))
      (node (ref "D6") (pin "1") (pinfunction "A_1") (pintype "passive"))
      (node (ref "D7") (pin "1") (pinfunction "A_1") (pintype "passive"))
      (node (ref "D8") (pin "1") (pinfunction "A_1") (pintype "passive"))
      (node (ref "Q1") (pin "2") (pinfunction "E_2") (pintype "passive"))
      (node (ref "Q2") (pin "2") (pinfunction "E_2") (pintype "passive"))
      (node (ref "Q3") (pin "2") (pinfunction "E_2") (pintype "passive"))
      (node (ref "Q4") (pin "2") (pinfunction "E_2") (pintype "passive"))
      (node (ref "Q6") (pin "2") (pinfunction "E_2") (pintype "passive"))
      (node (ref "Q7") (pin "2") (pinfunction "E_2") (pintype "passive"))
      (node (ref "Q8") (pin "2") (pinfunction "E_2") (pintype "passive"))
      (node (ref "Q9") (pin "2") (pinfunction "E_2") (pintype "passive"))
      (node (ref "R1") (pin "1") (pinfunction "1_1") (pintype "passive"))
      (node (ref "R19") (pin "1") (pinfunction "1_1") (pintype "passive"))
      (node (ref "R37") (pin "1") (pinfunction "1_1") (pintype "passive"))
      (node (ref "R38") (pin "1") (pinfunction "1_1") (pintype "passive"))
      (node (ref "R45") (pin "1") (pinfunction "1_1") (pintype "passive"))
      (node (ref "R46") (pin "1") (pinfunction "1_1") (pintype "passive"))
      (node (ref "R8") (pin "1") (pinfunction "1_1") (pintype "passive"))
      (node (ref "R9") (pin "1") (pinfunction "1_1") (pintype "passive"))
      (node (ref "U1") (pin "4") (pinfunction "D_4") (pintype "passive"))
      (node (ref "U1") (pin "5") (pinfunction "GND_5") (pintype "passive"))
      (node (ref "U10") (pin "4") (pinfunction "D_4") (pintype "passive"))
      (node (ref "U10") (pin "5") (pinfunction "GND_5") (pintype "passive"))
      (node (ref "U11") (pin "4") (pinfunction "D_4") (pintype "passive"))
      (node (ref "U11") (pin "5") (pinfunction "GND_5") (pintype "passive"))
      (node (ref "U12") (pin "4") (pintype "passive"))
      (node (ref "U13") (pin "5") (pinfunction "GND2_5") (pintype "passive"))
      (node (ref "U14") (pin "5") (pinfunction "GND2_5") (pintype "passive"))
      (node (ref "U15") (pin "4") (pinfunction "D_4") (pintype "passive"))
      (node (ref "U15") (pin "5") (pinfunction "GND_5") (pintype "passive"))
      (node (ref "U16") (pin "4") (pinfunction "D_4") (pintype "passive"))
      (node (ref "U16") (pin "5") (pinfunction "GND_5") (pintype "passive"))
      (node (ref "U17") (pin "5") (pinfunction "GND2_5") (pintype "passive"))
      (node (ref "U18") (pin "5") (pinfunction "GND2_5") (pintype "passive"))
      (node (ref "U2") (pin "5") (pinfunction "GND2_5") (pintype "passive"))
      (node (ref "U3") (pin "5") (pinfunction "GND2_5") (pintype "passive"))
      (node (ref "U4") (pin "5") (pinfunction "GND2_5") (pintype "passive"))
      (node (ref "U5") (pin "5") (pinfunction "GND2_5") (pintype "passive"))
      (node (ref "U7") (pin "4") (pinfunction "D_4") (pintype "passive"))
      (node (ref "U7") (pin "5") (pinfunction "GND_5") (pintype "passive"))
      (node (ref "U8") (pin "4") (pinfunction "D_4") (pintype "passive"))
      (node (ref "U8") (pin "5") (pinfunction "GND_5") (pintype "passive"))
      (node (ref "U9") (pin "4") (pinfunction "D_4") (pintype "passive"))
      (node (ref "U9") (pin "5") (pinfunction "GND_5") (pintype "passive"))
    )
    (net (code "39") (name "EARTH") (class "Default")
      (node (ref "C70") (pin "2") (pinfunction "2_2") (pintype "passive"))
    )
    (net (code "40") (name "GND") (class "Default")
      (node (ref "C11") (pin "1") (pinfunction "1_1") (pintype "passive"))
      (node (ref "C12") (pin "2") (pinfunction "2_2") (pintype "passive"))
      (node (ref "C13") (pin "2") (pinfunction "2_2") (pintype "passive"))
      (node (ref "C2") (pin "1") (pinfunction "1_1") (pintype "passive"))
      (node (ref "C20") (pin "1") (pinfunction "1_1") (pintype "passive"))
      (node (ref "C22") (pin "1") (pinfunction "1_1") (pintype "passive"))
      (node (ref "C26") (pin "1") (pinfunction "1_1") (pintype "passive"))
      (node (ref "C29") (pin "1") (pinfunction "1_1") (pintype "passive"))
      (node (ref "C30") (pin "2") (pinfunction "2_2") (pintype "passive"))
      (node (ref "C31") (pin "1") (pinfunction "1_1") (pintype "passive"))
      (node (ref "C4") (pin "1") (pinfunction "1_1") (pintype "passive"))
      (node (ref "C65") (pin "2") (pinfunction "2_2") (pintype "passive"))
      (node (ref "C66") (pin "2") (pinfunction "2_2") (pintype "passive"))
      (node (ref "C8") (pin "1") (pinfunction "1_1") (pintype "passive"))
      (node (ref "D9") (pin "1") (pinfunction "A_1") (pintype "passive"))
      (node (ref "P5") (pin "1") (pinfunction "1_1") (pintype "passive"))
      (node (ref "Q5") (pin "1") (pinfunction "G_1") (pintype "passive"))
      (node (ref "R16") (pin "2") (pinfunction "2_2") (pintype "passive"))
      (node (ref "U12") (pin "2") (pintype "passive"))
      (node (ref "U13") (pin "4") (pinfunction "GND1_4") (pintype "passive"))
      (node (ref "U14") (pin "4") (pinfunction "GND1_4") (pintype "passive"))
      (node (ref "U17") (pin "4") (pinfunction "GND1_4") (pintype "passive"))
      (node (ref "U18") (pin "4") (pinfunction "GND1_4") (pintype "passive"))
      (node (ref "U19") (pin "1") (pinfunction "GND_1") (pintype "passive"))
      (node (ref "U2") (pin "4") (pinfunction "GND1_4") (pintype "passive"))
      (node (ref "U3") (pin "4") (pinfunction "GND1_4") (pintype "passive"))
      (node (ref "U4") (pin "4") (pinfunction "GND1_4") (pintype "passive"))
      (node (ref "U5") (pin "4") (pinfunction "GND1_4") (pintype "passive"))
    )
    (net (code "41") (name "Net-(C65-Pad1)") (class "Default")
      (node (ref "C65") (pin "1") (pinfunction "1_1") (pintype "passive"))
      (node (ref "C66") (pin "1") (pinfunction "1_1") (pintype "passive"))
      (node (ref "L4") (pin "2") (pinfunction "2_2") (pintype "passive"))
      (node (ref "U12") (pin "1") (pintype "passive"))
    )
    (net (code "42") (name "Net-(C67-Pad2)") (class "Default")
      (node (ref "C67") (pin "2") (pinfunction "2_2") (pintype "passive"))
      (node (ref "R16") (pin "1") (pinfunction "1_1") (pintype "passive"))
    )
    (net (code "43") (name "Net-(D9-K)") (class "Default")
      (node (ref "D9") (pin "2") (pinfunction "K_2") (pintype "passive"))
      (node (ref "F2") (pin "1") (pinfunction "1_1") (pintype "passive"))
      (node (ref "Q5") (pin "3") (pinfunction "D_3") (pintype "passive"))
    )
    (net (code "44") (name "Net-(Q1-B)") (class "Default")
      (node (ref "Q1") (pin "1") (pinfunction "B_1") (pintype "passive"))
      (node (ref "R61") (pin "2") (pinfunction "2_2") (pintype "passive"))
    )
    (net (code "45") (name "Net-(Q1-C)") (class "Default")
      (node (ref "Q1") (pin "3") (pinfunction "C_3") (pintype "passive"))
      (node (ref "R63") (pin "1") (pinfunction "1_1") (pintype "passive"))
      (node (ref "U7") (pin "2") (pinfunction "~{RE}_2") (pintype "passive"))
      (node (ref "U7") (pin "3") (pinfunction "DE_3") (pintype "passive"))
    )
    (net (code "46") (name "Net-(Q2-B)") (class "Default")
      (node (ref "Q2") (pin "1") (pinfunction "B_1") (pintype "passive"))
      (node (ref "R64") (pin "2") (pinfunction "2_2") (pintype "passive"))
    )
    (net (code "47") (name "Net-(Q2-C)") (class "Default")
      (node (ref "Q2") (pin "3") (pinfunction "C_3") (pintype "passive"))
      (node (ref "R66") (pin "1") (pinfunction "1_1") (pintype "passive"))
      (node (ref "U8") (pin "2") (pinfunction "~{RE}_2") (pintype "passive"))
      (node (ref "U8") (pin "3") (pinfunction "DE_3") (pintype "passive"))
    )
    (net (code "48") (name "Net-(Q3-B)") (class "Default")
      (node (ref "Q3") (pin "1") (pinfunction "B_1") (pintype "passive"))
      (node (ref "R65") (pin "2") (pinfunction "2_2") (pintype "passive"))
    )
    (net (code "49") (name "Net-(Q3-C)") (class "Default")
      (node (ref "Q3") (pin "3") (pinfunction "C_3") (pintype "passive"))
      (node (ref "R67") (pin "1") (pinfunction "1_1") (pintype "passive"))
      (node (ref "U9") (pin "2") (pinfunction "~{RE}_2") (pintype "passive"))
      (node (ref "U9") (pin "3") (pinfunction "DE_3") (pintype "passive"))
    )
    (net (code "50") (name "Net-(Q4-B)") (class "Default")
      (node (ref "Q4") (pin "1") (pinfunction "B_1") (pintype "passive"))
      (node (ref "R43") (pin "2") (pinfunction "2_2") (pintype "passive"))
    )
    (net (code "51") (name "Net-(Q4-C)") (class "Default")
      (node (ref "Q4") (pin "3") (pinfunction "C_3") (pintype "passive"))
      (node (ref "R62") (pin "1") (pinfunction "1_1") (pintype "passive"))
      (node (ref "U1") (pin "2") (pinfunction "~{RE}_2") (pintype "passive"))
      (node (ref "U1") (pin "3") (pinfunction "DE_3") (pintype "passive"))
    )
    (net (code "52") (name "Net-(Q6-B)") (class "Default")
      (node (ref "Q6") (pin "1") (pinfunction "B_1") (pintype "passive"))
      (node (ref "R69") (pin "2") (pinfunction "2_2") (pintype "passive"))
    )
    (net (code "53") (name "Net-(Q6-C)") (class "Default")
      (node (ref "Q6") (pin "3") (pinfunction "C_3") (pintype "passive"))
      (node (ref "R71") (pin "1") (pinfunction "1_1") (pintype "passive"))
      (node (ref "U10") (pin "2") (pinfunction "~{RE}_2") (pintype "passive"))
      (node (ref "U10") (pin "3") (pinfunction "DE_3") (pintype "passive"))
    )
    (net (code "54") (name "Net-(Q7-B)") (class "Default")
      (node (ref "Q7") (pin "1") (pinfunction "B_1") (pintype "passive"))
      (node (ref "R70") (pin "2") (pinfunction "2_2") (pintype "passive"))
    )
    (net (code "55") (name "Net-(Q7-C)") (class "Default")
      (node (ref "Q7") (pin "3") (pinfunction "C_3") (pintype "passive"))
      (node (ref "R72") (pin "1") (pinfunction "1_1") (pintype "passive"))
      (node (ref "U11") (pin "2") (pinfunction "~{RE}_2") (pintype "passive"))
      (node (ref "U11") (pin "3") (pinfunction "DE_3") (pintype "passive"))
    )
    (net (code "56") (name "Net-(Q8-B)") (class "Default")
      (node (ref "Q8") (pin "1") (pinfunction "B_1") (pintype "passive"))
      (node (ref "R73") (pin "2") (pinfunction "2_2") (pintype "passive"))
    )
    (net (code "57") (name "Net-(Q8-C)") (class "Default")
      (node (ref "Q8") (pin "3") (pinfunction "C_3") (pintype "passive"))
      (node (ref "R75") (pin "1") (pinfunction "1_1") (pintype "passive"))
      (node (ref "U15") (pin "2") (pinfunction "~{RE}_2") (pintype "passive"))
      (node (ref "U15") (pin "3") (pinfunction "DE_3") (pintype "passive"))
    )
    (net (code "58") (name "Net-(Q9-B)") (class "Default")
      (node (ref "Q9") (pin "1") (pinfunction "B_1") (pintype "passive"))
      (node (ref "R74") (pin "2") (pinfunction "2_2") (pintype "passive"))
    )
    (net (code "59") (name "Net-(Q9-C)") (class "Default")
      (node (ref "Q9") (pin "3") (pinfunction "C_3") (pintype "passive"))
      (node (ref "R76") (pin "1") (pinfunction "1_1") (pintype "passive"))
      (node (ref "U16") (pin "2") (pinfunction "~{RE}_2") (pintype "passive"))
      (node (ref "U16") (pin "3") (pinfunction "DE_3") (pintype "passive"))
    )
    (net (code "60") (name "Net-(U1-A)") (class "Default")
      (node (ref "F4") (pin "2") (pinfunction "2_2") (pintype "passive"))
      (node (ref "R6") (pin "1") (pinfunction "1_1") (pintype "passive"))
      (node (ref "U1") (pin "6") (pinfunction "A_6") (pintype "passive"))
    )
    (net (code "61") (name "Net-(U1-B)") (class "Default")
      (node (ref "F1") (pin "2") (pinfunction "2_2") (pintype "passive"))
      (node (ref "R19") (pin "2") (pinfunction "2_2") (pintype "passive"))
      (node (ref "U1") (pin "7") (pinfunction "B_7") (pintype "passive"))
    )
    (net (code "62") (name "Net-(U1-R)") (class "Default")
      (node (ref "U1") (pin "1") (pinfunction "R_1") (pintype "passive"))
      (node (ref "U2") (pin "7") (pinfunction "VIA_7") (pintype "passive"))
    )
    (net (code "63") (name "Net-(U2-VOB)") (class "Default")
      (node (ref "R43") (pin "1") (pinfunction "1_1") (pintype "passive"))
      (node (ref "U2") (pin "6") (pinfunction "VOB_6") (pintype "passive"))
    )
    (net (code "64") (name "Net-(U3-VIA)") (class "Default")
      (node (ref "U3") (pin "7") (pinfunction "VIA_7") (pintype "passive"))
      (node (ref "U7") (pin "1") (pinfunction "R_1") (pintype "passive"))
    )
    (net (code "65") (name "Net-(U3-VOB)") (class "Default")
      (node (ref "R61") (pin "1") (pinfunction "1_1") (pintype "passive"))
      (node (ref "U3") (pin "6") (pinfunction "VOB_6") (pintype "passive"))
    )
    (net (code "66") (name "Net-(U4-VIA)") (class "Default")
      (node (ref "U4") (pin "7") (pinfunction "VIA_7") (pintype "passive"))
      (node (ref "U8") (pin "1") (pinfunction "R_1") (pintype "passive"))
    )
    (net (code "67") (name "Net-(U4-VOB)") (class "Default")
      (node (ref "R64") (pin "1") (pinfunction "1_1") (pintype "passive"))
      (node (ref "U4") (pin "6") (pinfunction "VOB_6") (pintype "passive"))
    )
    (net (code "68") (name "Net-(U5-VIA)") (class "Default")
      (node (ref "U5") (pin "7") (pinfunction "VIA_7") (pintype "passive"))
      (node (ref "U9") (pin "1") (pinfunction "R_1") (pintype "passive"))
    )
    (net (code "69") (name "Net-(U5-VOB)") (class "Default")
      (node (ref "R65") (pin "1") (pinfunction "1_1") (pintype "passive"))
      (node (ref "U5") (pin "6") (pinfunction "VOB_6") (pintype "passive"))
    )
    (net (code "70") (name "Net-(U7-A)") (class "Default")
      (node (ref "F5") (pin "2") (pinfunction "2_2") (pintype "passive"))
      (node (ref "R7") (pin "1") (pinfunction "1_1") (pintype "passive"))
      (node (ref "U7") (pin "6") (pinfunction "A_6") (pintype "passive"))
    )
    (net (code "71") (name "Net-(U7-B)") (class "Default")
      (node (ref "F3") (pin "2") (pinfunction "2_2") (pintype "passive"))
      (node (ref "R1") (pin "2") (pinfunction "2_2") (pintype "passive"))
      (node (ref "U7") (pin "7") (pinfunction "B_7") (pintype "passive"))
    )
    (net (code "72") (name "Net-(U8-A)") (class "Default")
      (node (ref "F8") (pin "2") (pinfunction "2_2") (pintype "passive"))
      (node (ref "R14") (pin "1") (pinfunction "1_1") (pintype "passive"))
      (node (ref "U8") (pin "6") (pinfunction "A_6") (pintype "passive"))
    )
    (net (code "73") (name "Net-(U8-B)") (class "Default")
      (node (ref "F6") (pin "2") (pinfunction "2_2") (pintype "passive"))
      (node (ref "R8") (pin "2") (pinfunction "2_2") (pintype "passive"))
      (node (ref "U8") (pin "7") (pinfunction "B_7") (pintype "passive"))
    )
    (net (code "74") (name "Net-(U9-A)") (class "Default")
      (node (ref "F9") (pin "2") (pinfunction "2_2") (pintype "passive"))
      (node (ref "R15") (pin "1") (pinfunction "1_1") (pintype "passive"))
      (node (ref "U9") (pin "6") (pinfunction "A_6") (pintype "passive"))
    )
    (net (code "75") (name "Net-(U9-B)") (class "Default")
      (node (ref "F7") (pin "2") (pinfunction "2_2") (pintype "passive"))
      (node (ref "R9") (pin "2") (pinfunction "2_2") (pintype "passive"))
      (node (ref "U9") (pin "7") (pinfunction "B_7") (pintype "passive"))
    )
    (net (code "76") (name "Net-(U10-A)") (class "Default")
      (node (ref "F12") (pin "2") (pinfunction "2_2") (pintype "passive"))
      (node (ref "R68") (pin "1") (pinfunction "1_1") (pintype "passive"))
      (node (ref "U10") (pin "6") (pinfunction "A_6") (pintype "passive"))
    )
    (net (code "77") (name "Net-(U10-B)") (class "Default")
      (node (ref "F10") (pin "2") (pinfunction "2_2") (pintype "passive"))
      (node (ref "R37") (pin "2") (pinfunction "2_2") (pintype "passive"))
      (node (ref "U10") (pin "7") (pinfunction "B_7") (pintype "passive"))
    )
    (net (code "78") (name "Net-(U10-R)") (class "Default")
      (node (ref "U10") (pin "1") (pinfunction "R_1") (pintype "passive"))
      (node (ref "U13") (pin "7") (pinfunction "VIA_7") (pintype "passive"))
    )
    (net (code "79") (name "Net-(U11-A)") (class "Default")
      (node (ref "F13") (pin "2") (pinfunction "2_2") (pintype "passive"))
      (node (ref "R44") (pin "1") (pinfunction "1_1") (pintype "passive"))
      (node (ref "U11") (pin "6") (pinfunction "A_6") (pintype "passive"))
    )
    (net (code "80") (name "Net-(U11-B)") (class "Default")
      (node (ref "F11") (pin "2") (pinfunction "2_2") (pintype "passive"))
      (node (ref "R38") (pin "2") (pinfunction "2_2") (pintype "passive"))
      (node (ref "U11") (pin "7") (pinfunction "B_7") (pintype "passive"))
    )
    (net (code "81") (name "Net-(U11-R)") (class "Default")
      (node (ref "U11") (pin "1") (pinfunction "R_1") (pintype "passive"))
      (node (ref "U14") (pin "7") (pinfunction "VIA_7") (pintype "passive"))
    )
    (net (code "82") (name "Net-(U13-VOB)") (class "Default")
      (node (ref "R69") (pin "1") (pinfunction "1_1") (pintype "passive"))
      (node (ref "U13") (pin "6") (pinfunction "VOB_6") (pintype "passive"))
    )
    (net (code "83") (name "Net-(U14-VOB)") (class "Default")
      (node (ref "R70") (pin "1") (pinfunction "1_1") (pintype "passive"))
      (node (ref "U14") (pin "6") (pinfunction "VOB_6") (pintype "passive"))
    )
    (net (code "84") (name "Net-(U15-A)") (class "Default")
      (node (ref "F16") (pin "2") (pinfunction "2_2") (pintype "passive"))
      (node (ref "R51") (pin "1") (pinfunction "1_1") (pintype "passive"))
      (node (ref "U15") (pin "6") (pinfunction "A_6") (pintype "passive"))
    )
    (net (code "85") (name "Net-(U15-B)") (class "Default")
      (node (ref "F14") (pin "2") (pinfunction "2_2") (pintype "passive"))
      (node (ref "R45") (pin "2") (pinfunction "2_2") (pintype "passive"))
      (node (ref "U15") (pin "7") (pinfunction "B_7") (pintype "passive"))
    )
    (net (code "86") (name "Net-(U15-R)") (class "Default")
      (node (ref "U15") (pin "1") (pinfunction "R_1") (pintype "passive"))
      (node (ref "U17") (pin "7") (pinfunction "VIA_7") (pintype "passive"))
    )
    (net (code "87") (name "Net-(U16-A)") (class "Default")
      (node (ref "F17") (pin "2") (pinfunction "2_2") (pintype "passive"))
      (node (ref "R52") (pin "1") (pinfunction "1_1") (pintype "passive"))
      (node (ref "U16") (pin "6") (pinfunction "A_6") (pintype "passive"))
    )
    (net (code "88") (name "Net-(U16-B)") (class "Default")
      (node (ref "F15") (pin "2") (pinfunction "2_2") (pintype "passive"))
      (node (ref "R46") (pin "2") (pinfunction "2_2") (pintype "passive"))
      (node (ref "U16") (pin "7") (pinfunction "B_7") (pintype "passive"))
    )
    (net (code "89") (name "Net-(U16-R)") (class "Default")
      (node (ref "U16") (pin "1") (pinfunction "R_1") (pintype "passive"))
      (node (ref "U18") (pin "7") (pinfunction "VIA_7") (pintype "passive"))
    )
    (net (code "90") (name "Net-(U17-VOB)") (class "Default")
      (node (ref "R73") (pin "1") (pinfunction "1_1") (pintype "passive"))
      (node (ref "U17") (pin "6") (pinfunction "VOB_6") (pintype "passive"))
    )
    (net (code "91") (name "Net-(U18-VOB)") (class "Default")
      (node (ref "R74") (pin "1") (pinfunction "1_1") (pintype "passive"))
      (node (ref "U18") (pin "6") (pinfunction "VOB_6") (pintype "passive"))
    )
    (net (code "92") (name "Net-(U19-V3)") (class "Default")
      (node (ref "C30") (pin "1") (pinfunction "1_1") (pintype "passive"))
      (node (ref "U19") (pin "4") (pinfunction "V3_4") (pintype "passive"))
    )
    (net (code "93") (name "VCC_5V_485") (class "Default")
      (node (ref "C1") (pin "2") (pinfunction "2_2") (pintype "passive"))
      (node (ref "C10") (pin "2") (pinfunction "2_2") (pintype "passive"))
      (node (ref "C14") (pin "1") (pinfunction "1_1") (pintype "passive"))
      (node (ref "C18") (pin "2") (pinfunction "2_2") (pintype "passive"))
      (node (ref "C19") (pin "2") (pinfunction "2_2") (pintype "passive"))
      (node (ref "C21") (pin "2") (pinfunction "2_2") (pintype "passive"))
      (node (ref "C23") (pin "2") (pinfunction "2_2") (pintype "passive"))
      (node (ref "C24") (pin "2") (pinfunction "2_2") (pintype "passive"))
      (node (ref "C25") (pin "2") (pinfunction "2_2") (pintype "passive"))
      (node (ref "C27") (pin "2") (pinfunction "2_2") (pintype "passive"))
      (node (ref "C28") (pin "2") (pinfunction "2_2") (pintype "passive"))
      (node (ref "C3") (pin "2") (pinfunction "2_2") (pintype "passive"))
      (node (ref "C32") (pin "2") (pinfunction "2_2") (pintype "passive"))
      (node (ref "C5") (pin "2") (pinfunction "2_2") (pintype "passive"))
      (node (ref "C6") (pin "2") (pinfunction "2_2") (pintype "passive"))
      (node (ref "C68") (pin "1") (pinfunction "1_1") (pintype "passive"))
      (node (ref "C7") (pin "2") (pinfunction "2_2") (pintype "passive"))
      (node (ref "C9") (pin "2") (pinfunction "2_2") (pintype "passive"))
      (node (ref "R14") (pin "2") (pinfunction "2_2") (pintype "passive"))
      (node (ref "R15") (pin "2") (pinfunction "2_2") (pintype "passive"))
      (node (ref "R44") (pin "2") (pinfunction "2_2") (pintype "passive"))
      (node (ref "R51") (pin "2") (pinfunction "2_2") (pintype "passive"))
      (node (ref "R52") (pin "2") (pinfunction "2_2") (pintype "passive"))
      (node (ref "R6") (pin "2") (pinfunction "2_2") (pintype "passive"))
      (node (ref "R62") (pin "2") (pinfunction "2_2") (pintype "passive"))
      (node (ref "R63") (pin "2") (pinfunction "2_2") (pintype "passive"))
      (node (ref "R66") (pin "2") (pinfunction "2_2") (pintype "passive"))
      (node (ref "R67") (pin "2") (pinfunction "2_2") (pintype "passive"))
      (node (ref "R68") (pin "2") (pinfunction "2_2") (pintype "passive"))
      (node (ref "R7") (pin "2") (pinfunction "2_2") (pintype "passive"))
      (node (ref "R71") (pin "2") (pinfunction "2_2") (pintype "passive"))
      (node (ref "R72") (pin "2") (pinfunction "2_2") (pintype "passive"))
      (node (ref "R75") (pin "2") (pinfunction "2_2") (pintype "passive"))
      (node (ref "R76") (pin "2") (pinfunction "2_2") (pintype "passive"))
      (node (ref "U1") (pin "8") (pinfunction "VCC_8") (pintype "passive"))
      (node (ref "U10") (pin "8") (pinfunction "VCC_8") (pintype "passive"))
      (node (ref "U11") (pin "8") (pinfunction "VCC_8") (pintype "passive"))
      (node (ref "U12") (pin "6") (pintype "passive"))
      (node (ref "U13") (pin "8") (pinfunction "VDD2_8") (pintype "passive"))
      (node (ref "U14") (pin "8") (pinfunction "VDD2_8") (pintype "passive"))
      (node (ref "U15") (pin "8") (pinfunction "VCC_8") (pintype "passive"))
      (node (ref "U16") (pin "8") (pinfunction "VCC_8") (pintype "passive"))
      (node (ref "U17") (pin "8") (pinfunction "VDD2_8") (pintype "passive"))
      (node (ref "U18") (pin "8") (pinfunction "VDD2_8") (pintype "passive"))
      (node (ref "U2") (pin "8") (pinfunction "VDD2_8") (pintype "passive"))
      (node (ref "U3") (pin "8") (pinfunction "VDD2_8") (pintype "passive"))
      (node (ref "U4") (pin "8") (pinfunction "VDD2_8") (pintype "passive"))
      (node (ref "U5") (pin "8") (pinfunction "VDD2_8") (pintype "passive"))
      (node (ref "U7") (pin "8") (pinfunction "VCC_8") (pintype "passive"))
      (node (ref "U8") (pin "8") (pinfunction "VCC_8") (pintype "passive"))
      (node (ref "U9") (pin "8") (pinfunction "VCC_8") (pintype "passive"))
    )
    (net (code "94") (name "VIN") (class "Default")
      (node (ref "C31") (pin "2") (pinfunction "2_2") (pintype "passive"))
      (node (ref "C67") (pin "1") (pinfunction "1_1") (pintype "passive"))
      (node (ref "P5") (pin "2") (pinfunction "2_2") (pintype "passive"))
      (node (ref "Q5") (pin "2") (pinfunction "S_2") (pintype "passive"))
      (node (ref "U19") (pin "16") (pinfunction "VCC_16") (pintype "passive"))
    )
    (net (code "95") (name "unconnected-(U19-CTS#-Pad9)") (class "Default")
      (node (ref "U19") (pin "9") (pinfunction "CTS#_9") (pintype "passive"))
    )
    (net (code "96") (name "unconnected-(U19-DCD#-Pad12)") (class "Default")
      (node (ref "U19") (pin "12") (pinfunction "DCD#_12") (pintype "passive"))
    )
    (net (code "97") (name "unconnected-(U19-DSR#-Pad10)") (class "Default")
      (node (ref "U19") (pin "10") (pinfunction "DSR#_10") (pintype "passive"))
    )
    (net (code "98") (name "unconnected-(U19-DTR#-Pad13)") (class "Default")
      (node (ref "U19") (pin "13") (pinfunction "DTR#_13") (pintype "passive"))
    )
    (net (code "99") (name "unconnected-(U19-NC.-Pad7)") (class "Default")
      (node (ref "U19") (pin "7") (pinfunction "NC._7") (pintype "passive"))
    )
    (net (code "100") (name "unconnected-(U19-OUT#-Pad8)") (class "Default")
      (node (ref "U19") (pin "8") (pinfunction "OUT#_8") (pintype "passive"))
    )
    (net (code "101") (name "unconnected-(U19-R232-Pad15)") (class "Default")
      (node (ref "U19") (pin "15") (pinfunction "R232_15") (pintype "passive"))
    )
    (net (code "102") (name "unconnected-(U19-RI#-Pad11)") (class "Default")
      (node (ref "U19") (pin "11") (pinfunction "RI#_11") (pintype "passive"))
    )
    (net (code "103") (name "unconnected-(U19-RTS#-Pad14)") (class "Default")
      (node (ref "U19") (pin "14") (pinfunction "RTS#_14") (pintype "passive"))
    )
  )
)
